# reg-board.net
KiCad netlist of a schematic drawn in EAGLE
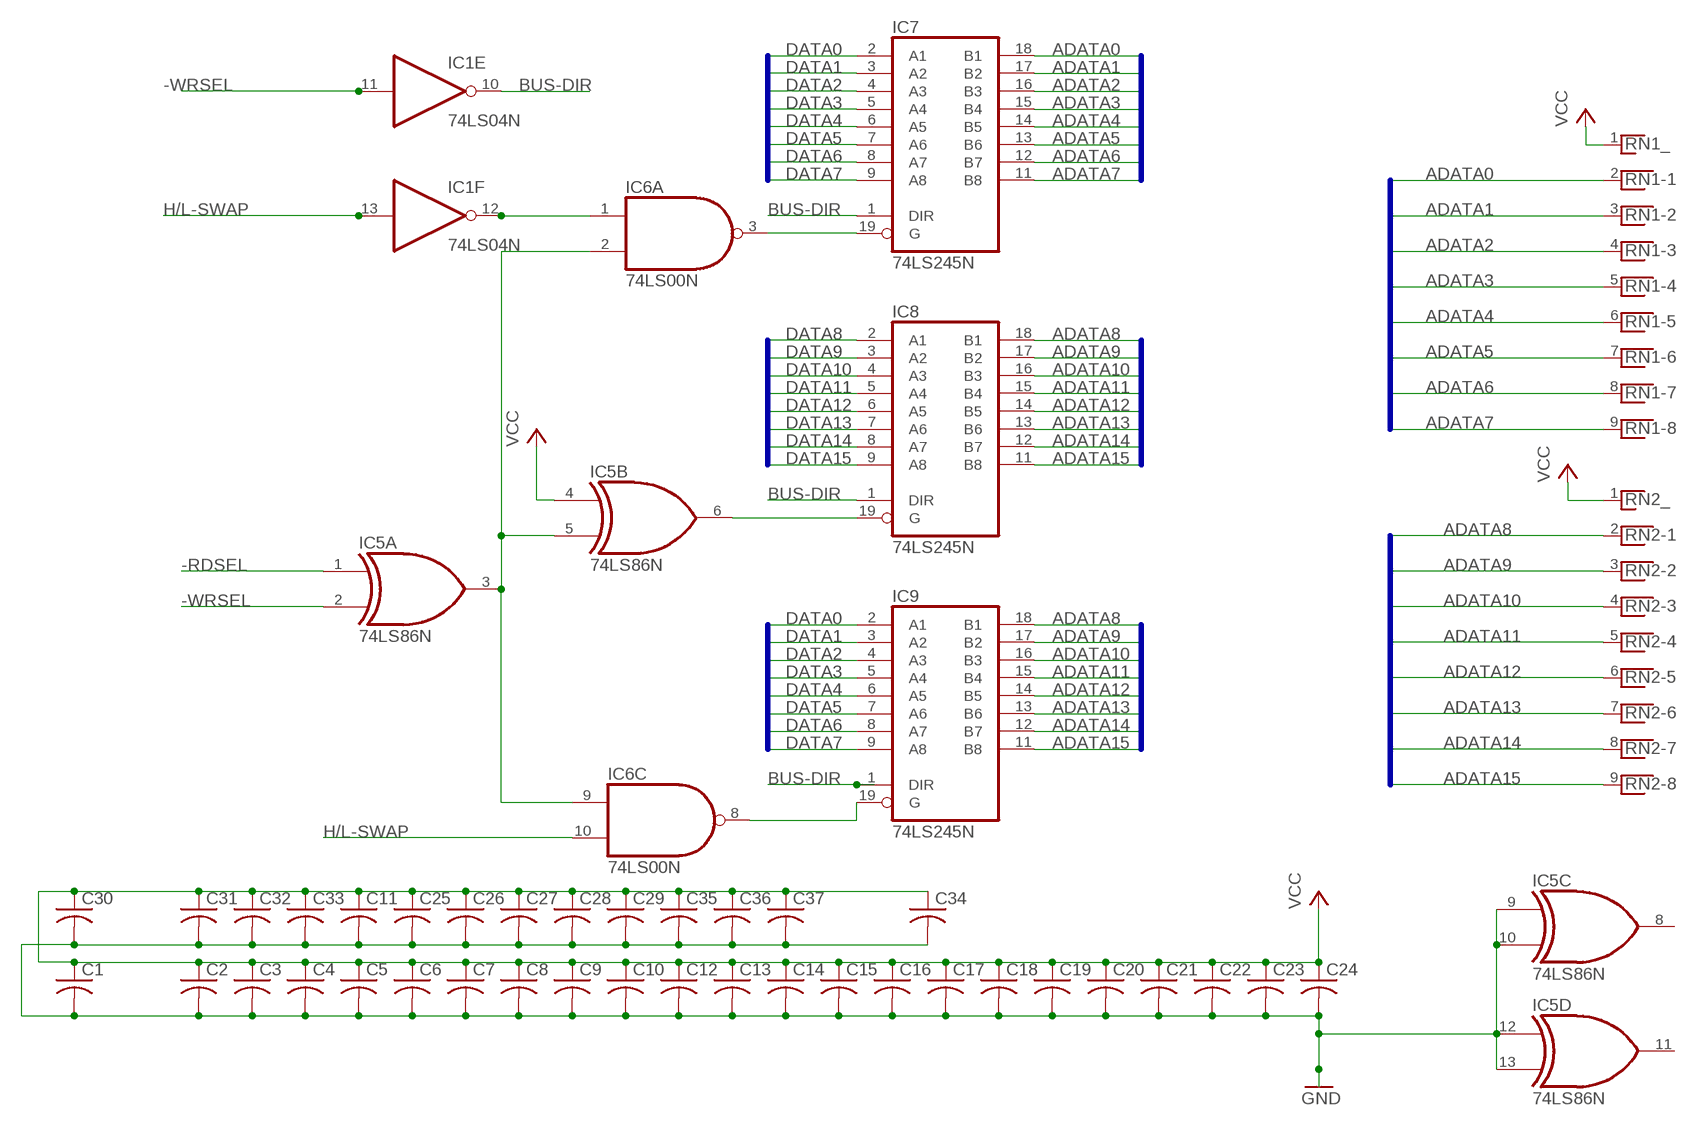
[diagram p0: schematic, sheet 1]
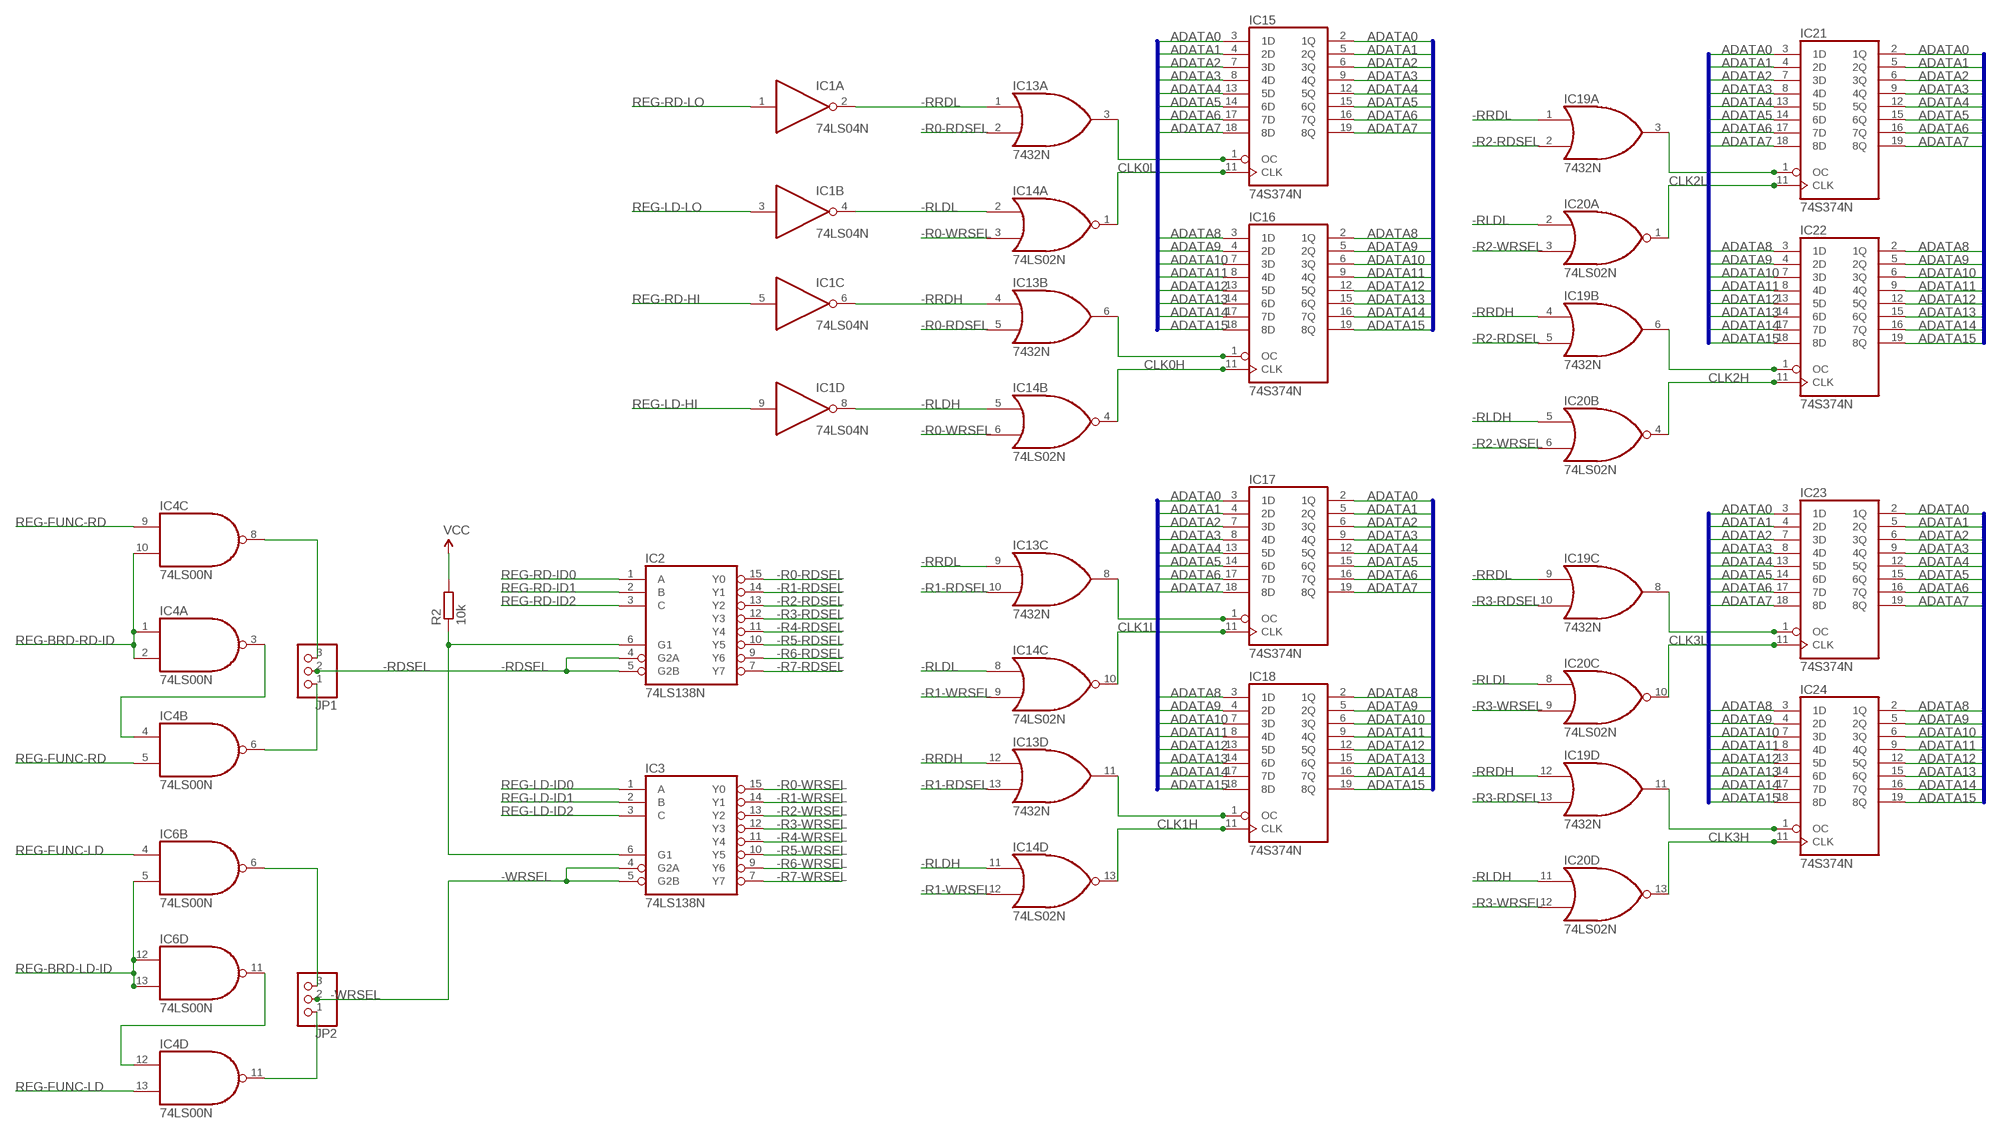
[diagram p1: schematic, sheet 2]
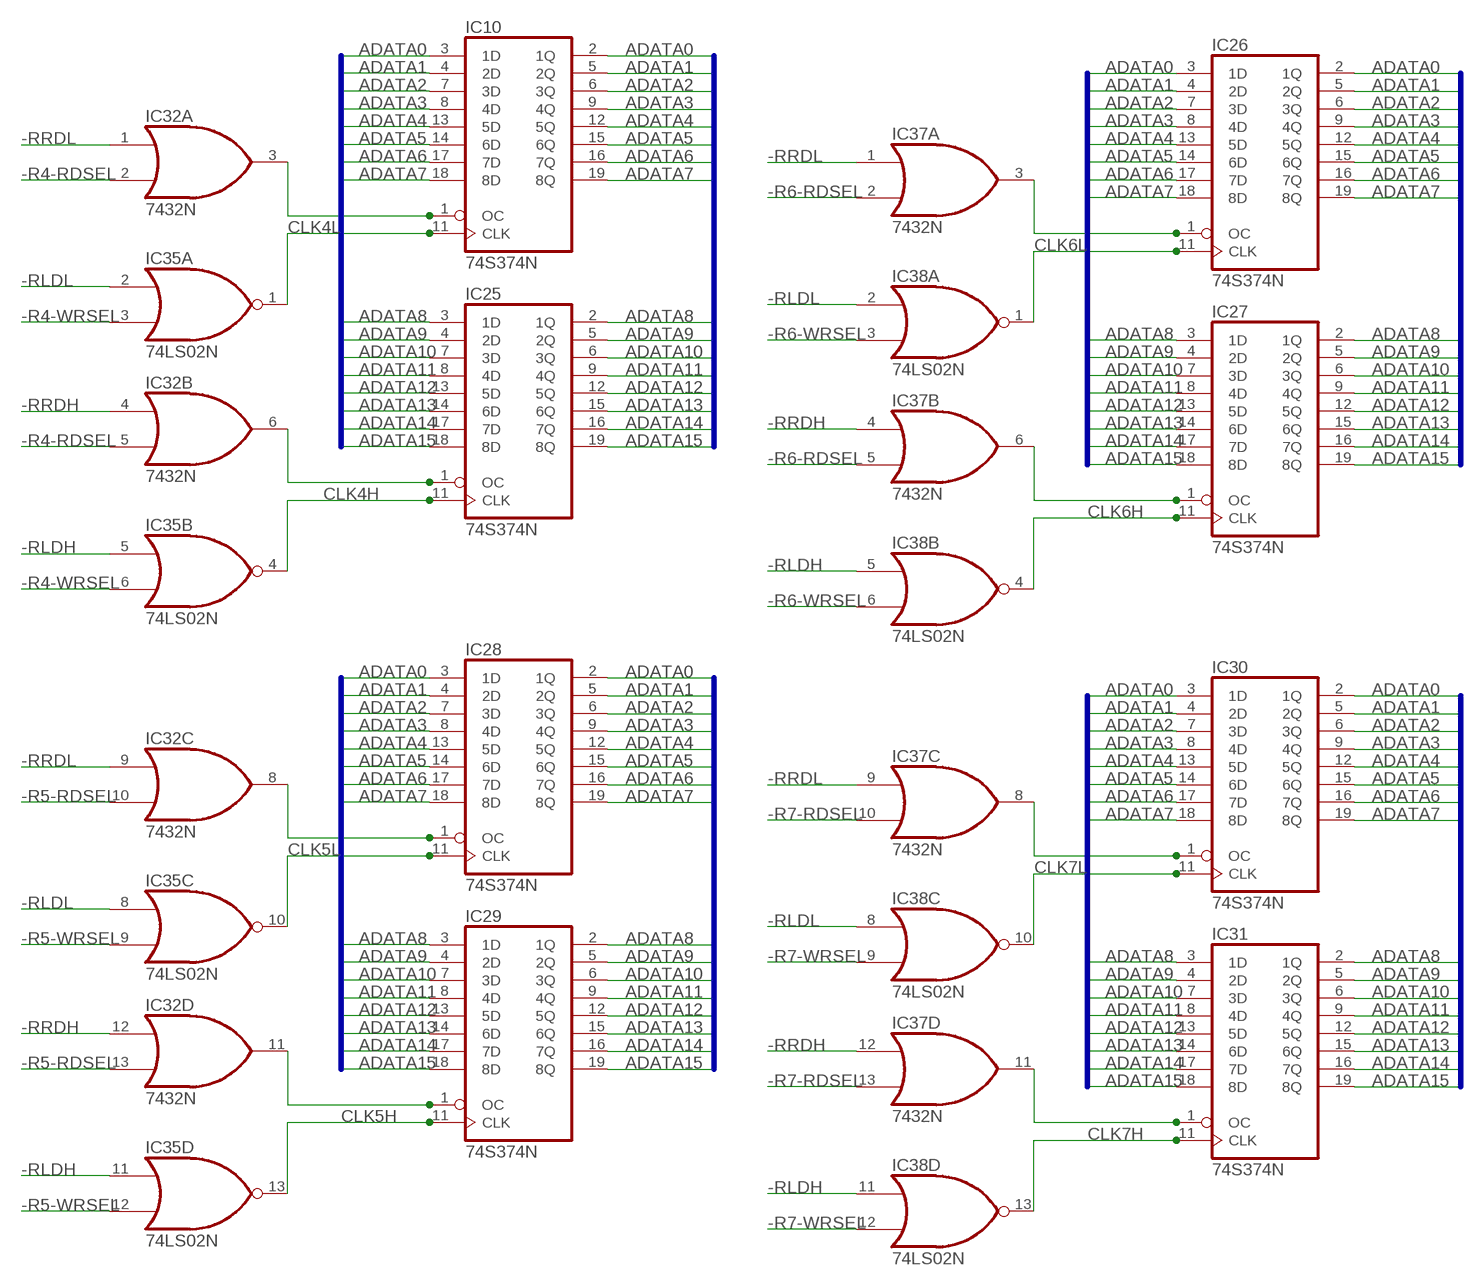
[diagram p2: schematic, sheet 3]
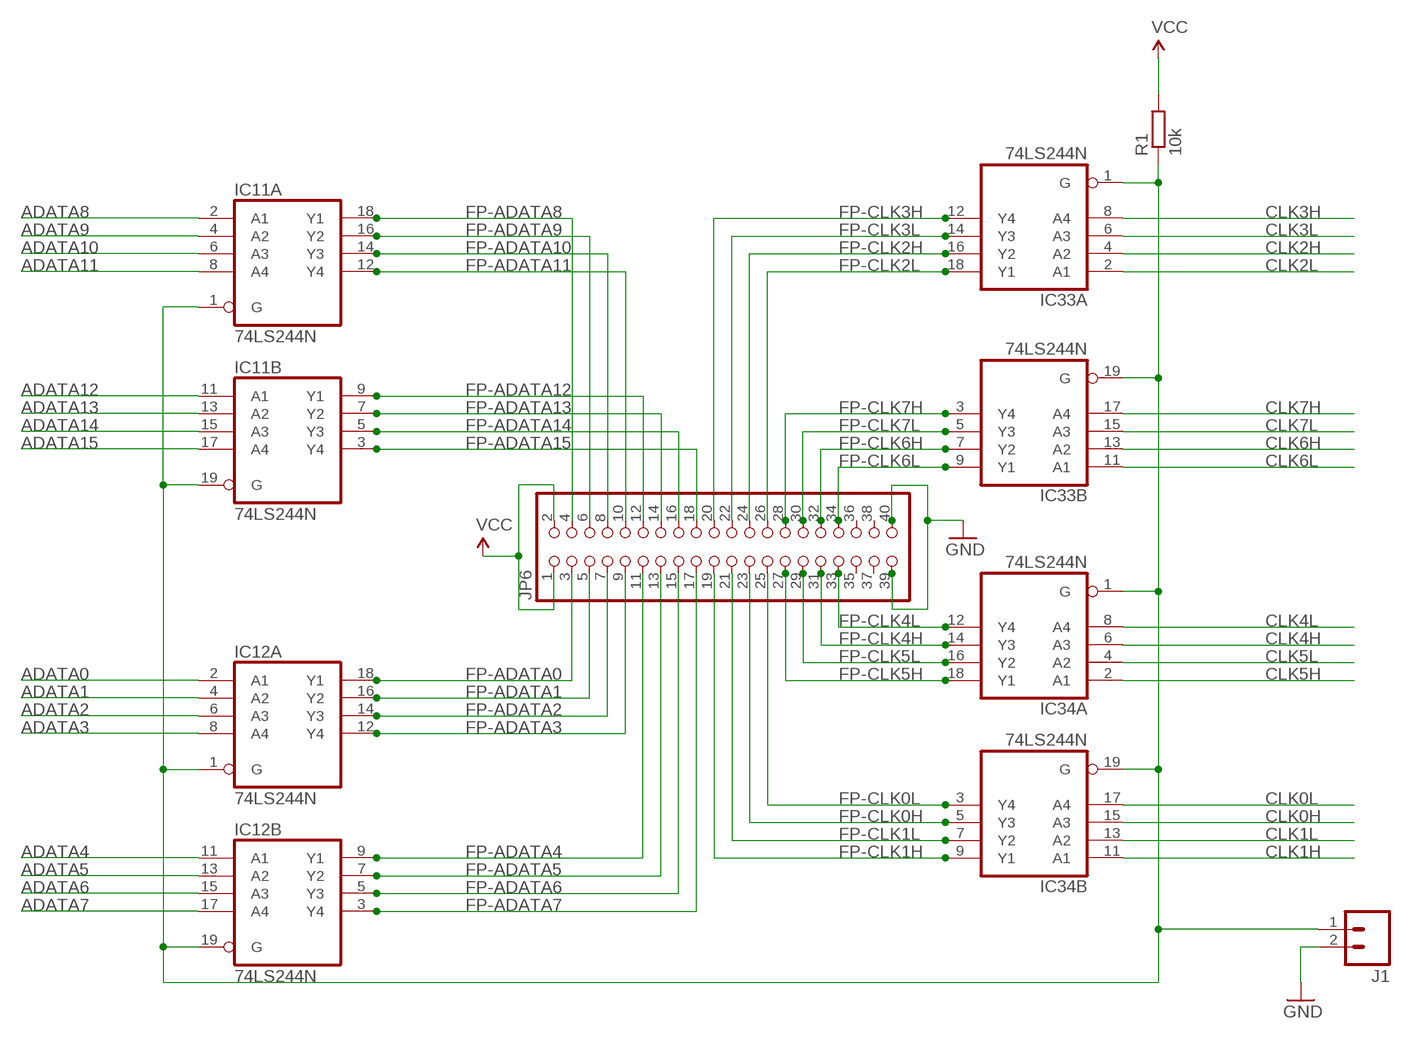
[diagram p3: schematic, sheet 4]
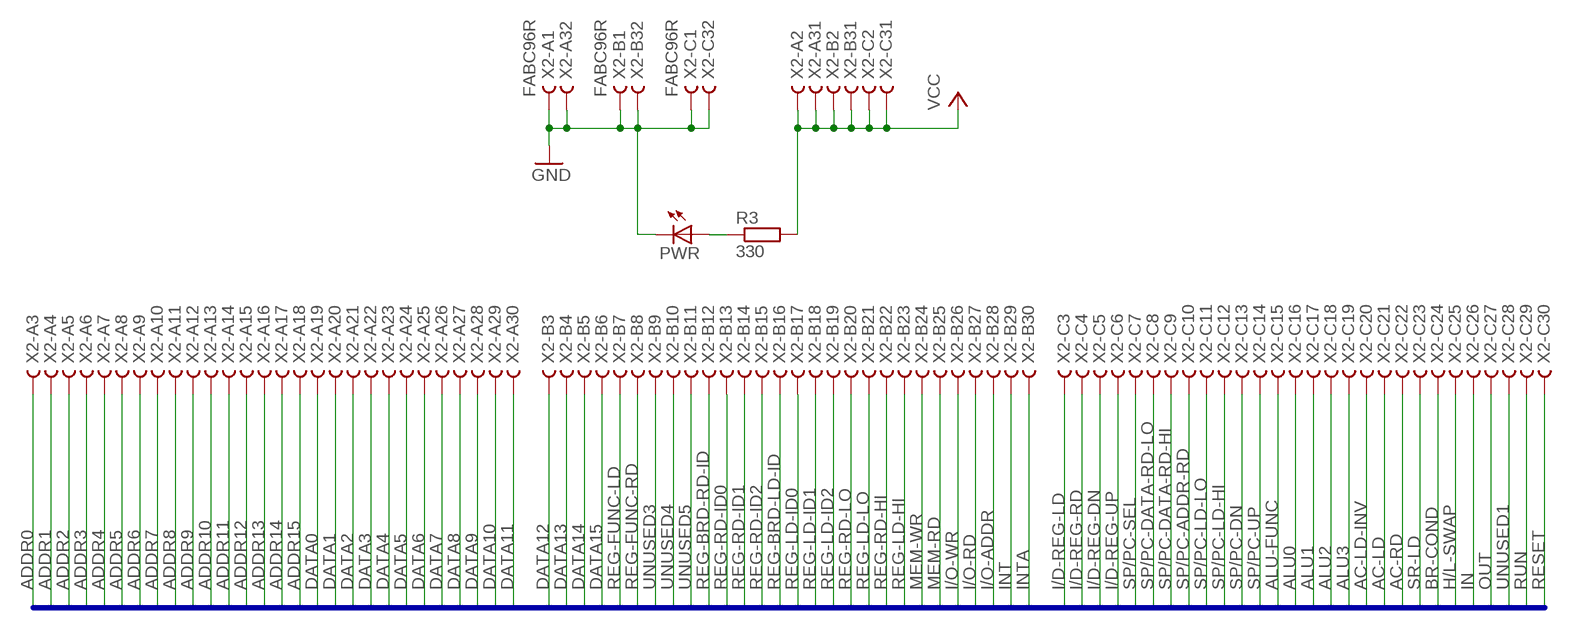
[diagram p4: schematic, sheet 5]

(export (version "E")
  (design (tool "Eeschema 10.0.6"))
  (components
    (comp (ref "IC11")
      (value "74LS244N")
      (footprint "eagle-import:DIL20")
      (libsource (lib "eagle-import") (part "74xx-us_74244NLS"))
    )
    (comp (ref "IC12")
      (value "74LS244N")
      (footprint "eagle-import:DIL20")
      (libsource (lib "eagle-import") (part "74xx-us_74244NLS"))
    )
    (comp (ref "IC33")
      (value "74LS244N")
      (footprint "eagle-import:DIL20")
      (libsource (lib "eagle-import") (part "74xx-us_74244NLS"))
    )
    (comp (ref "IC34")
      (value "74LS244N")
      (footprint "eagle-import:DIL20")
      (libsource (lib "eagle-import") (part "74xx-us_74244NLS"))
    )
    (comp (ref "J1")
      (value "M02PTH")
      (footprint "eagle-import:1X02")
      (libsource (lib "eagle-import") (part "M02PTH"))
    )
    (comp (ref "JP6")
      (value "PINHD-2X20")
      (footprint "eagle-import:2X20")
      (libsource (lib "eagle-import") (part "PINHD-2X20"))
    )
    (comp (ref "R1")
      (value "10k")
      (footprint "eagle-import:0207_10")
      (libsource (lib "eagle-import") (part "R0207/10"))
    )
    (comp (ref "PWR")
      (value "LED5MM")
      (footprint "eagle-import:LED5MM")
      (libsource (lib "eagle-import") (part "LED5MM"))
    )
    (comp (ref "R3")
      (value "330")
      (footprint "eagle-import:0207_10")
      (libsource (lib "eagle-import") (part "R0207/10"))
    )
    (comp (ref "X2")
      (value "FABC96R")
      (footprint "eagle-import:FABC96R")
      (libsource (lib "eagle-import") (part "FABC96R"))
    )
    (comp (ref "C1")
      (value "C-US025-040X050")
      (footprint "eagle-import:C025-040X050")
      (libsource (lib "eagle-import") (part "C-US025-040X050"))
    )
    (comp (ref "C2")
      (value "C-US025-040X050")
      (footprint "eagle-import:C025-040X050")
      (libsource (lib "eagle-import") (part "C-US025-040X050"))
    )
    (comp (ref "C3")
      (value "C-US025-040X050")
      (footprint "eagle-import:C025-040X050")
      (libsource (lib "eagle-import") (part "C-US025-040X050"))
    )
    (comp (ref "C4")
      (value "C-US025-040X050")
      (footprint "eagle-import:C025-040X050")
      (libsource (lib "eagle-import") (part "C-US025-040X050"))
    )
    (comp (ref "C5")
      (value "C-US025-040X050")
      (footprint "eagle-import:C025-040X050")
      (libsource (lib "eagle-import") (part "C-US025-040X050"))
    )
    (comp (ref "C6")
      (value "C-US025-040X050")
      (footprint "eagle-import:C025-040X050")
      (libsource (lib "eagle-import") (part "C-US025-040X050"))
    )
    (comp (ref "C7")
      (value "C-US025-040X050")
      (footprint "eagle-import:C025-040X050")
      (libsource (lib "eagle-import") (part "C-US025-040X050"))
    )
    (comp (ref "C8")
      (value "C-US025-040X050")
      (footprint "eagle-import:C025-040X050")
      (libsource (lib "eagle-import") (part "C-US025-040X050"))
    )
    (comp (ref "C9")
      (value "C-US025-040X050")
      (footprint "eagle-import:C025-040X050")
      (libsource (lib "eagle-import") (part "C-US025-040X050"))
    )
    (comp (ref "C10")
      (value "C-US025-040X050")
      (footprint "eagle-import:C025-040X050")
      (libsource (lib "eagle-import") (part "C-US025-040X050"))
    )
    (comp (ref "C11")
      (value "C-US025-040X050")
      (footprint "eagle-import:C025-040X050")
      (libsource (lib "eagle-import") (part "C-US025-040X050"))
    )
    (comp (ref "C12")
      (value "C-US025-040X050")
      (footprint "eagle-import:C025-040X050")
      (libsource (lib "eagle-import") (part "C-US025-040X050"))
    )
    (comp (ref "C13")
      (value "C-US025-040X050")
      (footprint "eagle-import:C025-040X050")
      (libsource (lib "eagle-import") (part "C-US025-040X050"))
    )
    (comp (ref "C14")
      (value "C-US025-040X050")
      (footprint "eagle-import:C025-040X050")
      (libsource (lib "eagle-import") (part "C-US025-040X050"))
    )
    (comp (ref "C15")
      (value "C-US025-040X050")
      (footprint "eagle-import:C025-040X050")
      (libsource (lib "eagle-import") (part "C-US025-040X050"))
    )
    (comp (ref "C16")
      (value "C-US025-040X050")
      (footprint "eagle-import:C025-040X050")
      (libsource (lib "eagle-import") (part "C-US025-040X050"))
    )
    (comp (ref "C17")
      (value "C-US025-040X050")
      (footprint "eagle-import:C025-040X050")
      (libsource (lib "eagle-import") (part "C-US025-040X050"))
    )
    (comp (ref "C18")
      (value "C-US025-040X050")
      (footprint "eagle-import:C025-040X050")
      (libsource (lib "eagle-import") (part "C-US025-040X050"))
    )
    (comp (ref "C19")
      (value "C-US025-040X050")
      (footprint "eagle-import:C025-040X050")
      (libsource (lib "eagle-import") (part "C-US025-040X050"))
    )
    (comp (ref "C20")
      (value "C-US025-040X050")
      (footprint "eagle-import:C025-040X050")
      (libsource (lib "eagle-import") (part "C-US025-040X050"))
    )
    (comp (ref "C21")
      (value "C-US025-040X050")
      (footprint "eagle-import:C025-040X050")
      (libsource (lib "eagle-import") (part "C-US025-040X050"))
    )
    (comp (ref "C22")
      (value "C-US025-040X050")
      (footprint "eagle-import:C025-040X050")
      (libsource (lib "eagle-import") (part "C-US025-040X050"))
    )
    (comp (ref "C23")
      (value "C-US025-040X050")
      (footprint "eagle-import:C025-040X050")
      (libsource (lib "eagle-import") (part "C-US025-040X050"))
    )
    (comp (ref "C24")
      (value "C-US025-040X050")
      (footprint "eagle-import:C025-040X050")
      (libsource (lib "eagle-import") (part "C-US025-040X050"))
    )
    (comp (ref "C25")
      (value "C-US025-040X050")
      (footprint "eagle-import:C025-040X050")
      (libsource (lib "eagle-import") (part "C-US025-040X050"))
    )
    (comp (ref "C26")
      (value "C-US025-040X050")
      (footprint "eagle-import:C025-040X050")
      (libsource (lib "eagle-import") (part "C-US025-040X050"))
    )
    (comp (ref "C27")
      (value "C-US025-040X050")
      (footprint "eagle-import:C025-040X050")
      (libsource (lib "eagle-import") (part "C-US025-040X050"))
    )
    (comp (ref "C28")
      (value "C-US025-040X050")
      (footprint "eagle-import:C025-040X050")
      (libsource (lib "eagle-import") (part "C-US025-040X050"))
    )
    (comp (ref "C29")
      (value "C-US025-040X050")
      (footprint "eagle-import:C025-040X050")
      (libsource (lib "eagle-import") (part "C-US025-040X050"))
    )
    (comp (ref "C30")
      (value "C-US025-040X050")
      (footprint "eagle-import:C025-040X050")
      (libsource (lib "eagle-import") (part "C-US025-040X050"))
    )
    (comp (ref "C31")
      (value "C-US025-040X050")
      (footprint "eagle-import:C025-040X050")
      (libsource (lib "eagle-import") (part "C-US025-040X050"))
    )
    (comp (ref "C32")
      (value "C-US025-040X050")
      (footprint "eagle-import:C025-040X050")
      (libsource (lib "eagle-import") (part "C-US025-040X050"))
    )
    (comp (ref "C33")
      (value "C-US025-040X050")
      (footprint "eagle-import:C025-040X050")
      (libsource (lib "eagle-import") (part "C-US025-040X050"))
    )
    (comp (ref "C34")
      (value "C-US025-040X050")
      (footprint "eagle-import:C025-040X050")
      (libsource (lib "eagle-import") (part "C-US025-040X050"))
    )
    (comp (ref "C35")
      (value "C-US025-040X050")
      (footprint "eagle-import:C025-040X050")
      (libsource (lib "eagle-import") (part "C-US025-040X050"))
    )
    (comp (ref "C36")
      (value "C-US025-040X050")
      (footprint "eagle-import:C025-040X050")
      (libsource (lib "eagle-import") (part "C-US025-040X050"))
    )
    (comp (ref "C37")
      (value "C-US025-040X050")
      (footprint "eagle-import:C025-040X050")
      (libsource (lib "eagle-import") (part "C-US025-040X050"))
    )
    (comp (ref "IC1")
      (value "74LS04N")
      (footprint "eagle-import:DIL14")
      (libsource (lib "eagle-import") (part "7404NLS"))
    )
    (comp (ref "IC5")
      (value "74LS86N")
      (footprint "eagle-import:DIL14")
      (libsource (lib "eagle-import") (part "7486NLS"))
    )
    (comp (ref "IC6")
      (value "74LS00N")
      (footprint "eagle-import:DIL14")
      (libsource (lib "eagle-import") (part "7400NLS"))
    )
    (comp (ref "IC7")
      (value "74LS245N")
      (footprint "eagle-import:DIL20")
      (libsource (lib "eagle-import") (part "74245NLS"))
    )
    (comp (ref "IC8")
      (value "74LS245N")
      (footprint "eagle-import:DIL20")
      (libsource (lib "eagle-import") (part "74245NLS"))
    )
    (comp (ref "IC9")
      (value "74LS245N")
      (footprint "eagle-import:DIL20")
      (libsource (lib "eagle-import") (part "74245NLS"))
    )
    (comp (ref "RN1")
      (value "RNX8")
      (footprint "eagle-import:RN-9")
      (libsource (lib "eagle-import") (part "RNX8"))
    )
    (comp (ref "RN2")
      (value "RNX8")
      (footprint "eagle-import:RN-9")
      (libsource (lib "eagle-import") (part "RNX8"))
    )
    (comp (ref "IC2")
      (value "74LS138N")
      (footprint "eagle-import:DIL16")
      (libsource (lib "eagle-import") (part "74138NLS"))
    )
    (comp (ref "IC3")
      (value "74LS138N")
      (footprint "eagle-import:DIL16")
      (libsource (lib "eagle-import") (part "74138NLS"))
    )
    (comp (ref "IC4")
      (value "74LS00N")
      (footprint "eagle-import:DIL14")
      (libsource (lib "eagle-import") (part "7400NLS"))
    )
    (comp (ref "IC13")
      (value "7432N")
      (footprint "eagle-import:DIL14")
      (libsource (lib "eagle-import") (part "7432N"))
    )
    (comp (ref "IC14")
      (value "74LS02N")
      (footprint "eagle-import:DIL14")
      (libsource (lib "eagle-import") (part "7402NLS"))
    )
    (comp (ref "IC15")
      (value "74S374N")
      (footprint "eagle-import:DIL20")
      (libsource (lib "eagle-import") (part "74374NS"))
    )
    (comp (ref "IC16")
      (value "74S374N")
      (footprint "eagle-import:DIL20")
      (libsource (lib "eagle-import") (part "74374NS"))
    )
    (comp (ref "IC17")
      (value "74S374N")
      (footprint "eagle-import:DIL20")
      (libsource (lib "eagle-import") (part "74374NS"))
    )
    (comp (ref "IC18")
      (value "74S374N")
      (footprint "eagle-import:DIL20")
      (libsource (lib "eagle-import") (part "74374NS"))
    )
    (comp (ref "IC19")
      (value "7432N")
      (footprint "eagle-import:DIL14")
      (libsource (lib "eagle-import") (part "7432N"))
    )
    (comp (ref "IC20")
      (value "74LS02N")
      (footprint "eagle-import:DIL14")
      (libsource (lib "eagle-import") (part "7402NLS"))
    )
    (comp (ref "IC21")
      (value "74S374N")
      (footprint "eagle-import:DIL20")
      (libsource (lib "eagle-import") (part "74374NS"))
    )
    (comp (ref "IC22")
      (value "74S374N")
      (footprint "eagle-import:DIL20")
      (libsource (lib "eagle-import") (part "74374NS"))
    )
    (comp (ref "IC23")
      (value "74S374N")
      (footprint "eagle-import:DIL20")
      (libsource (lib "eagle-import") (part "74374NS"))
    )
    (comp (ref "IC24")
      (value "74S374N")
      (footprint "eagle-import:DIL20")
      (libsource (lib "eagle-import") (part "74374NS"))
    )
    (comp (ref "JP1")
      (value "PINHD-1X3")
      (footprint "eagle-import:1X03")
      (libsource (lib "eagle-import") (part "PINHD-1X3"))
    )
    (comp (ref "JP2")
      (value "PINHD-1X3")
      (footprint "eagle-import:1X03")
      (libsource (lib "eagle-import") (part "PINHD-1X3"))
    )
    (comp (ref "R2")
      (value "10k")
      (footprint "eagle-import:0207_10")
      (libsource (lib "eagle-import") (part "R0207/10"))
    )
    (comp (ref "IC10")
      (value "74S374N")
      (footprint "eagle-import:DIL20")
      (libsource (lib "eagle-import") (part "74374NS"))
    )
    (comp (ref "IC25")
      (value "74S374N")
      (footprint "eagle-import:DIL20")
      (libsource (lib "eagle-import") (part "74374NS"))
    )
    (comp (ref "IC26")
      (value "74S374N")
      (footprint "eagle-import:DIL20")
      (libsource (lib "eagle-import") (part "74374NS"))
    )
    (comp (ref "IC27")
      (value "74S374N")
      (footprint "eagle-import:DIL20")
      (libsource (lib "eagle-import") (part "74374NS"))
    )
    (comp (ref "IC28")
      (value "74S374N")
      (footprint "eagle-import:DIL20")
      (libsource (lib "eagle-import") (part "74374NS"))
    )
    (comp (ref "IC29")
      (value "74S374N")
      (footprint "eagle-import:DIL20")
      (libsource (lib "eagle-import") (part "74374NS"))
    )
    (comp (ref "IC30")
      (value "74S374N")
      (footprint "eagle-import:DIL20")
      (libsource (lib "eagle-import") (part "74374NS"))
    )
    (comp (ref "IC31")
      (value "74S374N")
      (footprint "eagle-import:DIL20")
      (libsource (lib "eagle-import") (part "74374NS"))
    )
    (comp (ref "IC32")
      (value "7432N")
      (footprint "eagle-import:DIL14")
      (libsource (lib "eagle-import") (part "7432N"))
    )
    (comp (ref "IC35")
      (value "74LS02N")
      (footprint "eagle-import:DIL14")
      (libsource (lib "eagle-import") (part "7402NLS"))
    )
    (comp (ref "IC37")
      (value "7432N")
      (footprint "eagle-import:DIL14")
      (libsource (lib "eagle-import") (part "7432N"))
    )
    (comp (ref "IC38")
      (value "74LS02N")
      (footprint "eagle-import:DIL14")
      (libsource (lib "eagle-import") (part "7402NLS"))
    )
  )
  (nets
    (net (code "1") (name "-R0-RDSEL") (class "Default")
      (node (ref "IC13") (pin "2") (pinfunction "I1_2") (pintype "input"))
      (node (ref "IC13") (pin "5") (pinfunction "I1_5") (pintype "input"))
      (node (ref "IC2") (pin "15") (pinfunction "Y0_15") (pintype "output"))
    )
    (net (code "2") (name "-R0-WRSEL") (class "Default")
      (node (ref "IC14") (pin "3") (pinfunction "I1_3") (pintype "input"))
      (node (ref "IC14") (pin "6") (pinfunction "I1_6") (pintype "input"))
      (node (ref "IC3") (pin "15") (pinfunction "Y0_15") (pintype "output"))
    )
    (net (code "3") (name "-R1-RDSEL") (class "Default")
      (node (ref "IC13") (pin "10") (pinfunction "I1_10") (pintype "input"))
      (node (ref "IC13") (pin "13") (pinfunction "I1_13") (pintype "input"))
      (node (ref "IC2") (pin "14") (pinfunction "Y1_14") (pintype "output"))
    )
    (net (code "4") (name "-R1-WRSEL") (class "Default")
      (node (ref "IC14") (pin "12") (pinfunction "I1_12") (pintype "input"))
      (node (ref "IC14") (pin "9") (pinfunction "I1_9") (pintype "input"))
      (node (ref "IC3") (pin "14") (pinfunction "Y1_14") (pintype "output"))
    )
    (net (code "5") (name "-R2-RDSEL") (class "Default")
      (node (ref "IC19") (pin "2") (pinfunction "I1_2") (pintype "input"))
      (node (ref "IC19") (pin "5") (pinfunction "I1_5") (pintype "input"))
      (node (ref "IC2") (pin "13") (pinfunction "Y2_13") (pintype "output"))
    )
    (net (code "6") (name "-R2-WRSEL") (class "Default")
      (node (ref "IC20") (pin "3") (pinfunction "I1_3") (pintype "input"))
      (node (ref "IC20") (pin "6") (pinfunction "I1_6") (pintype "input"))
      (node (ref "IC3") (pin "13") (pinfunction "Y2_13") (pintype "output"))
    )
    (net (code "7") (name "-R3-RDSEL") (class "Default")
      (node (ref "IC19") (pin "10") (pinfunction "I1_10") (pintype "input"))
      (node (ref "IC19") (pin "13") (pinfunction "I1_13") (pintype "input"))
      (node (ref "IC2") (pin "12") (pinfunction "Y3_12") (pintype "output"))
    )
    (net (code "8") (name "-R3-WRSEL") (class "Default")
      (node (ref "IC20") (pin "12") (pinfunction "I1_12") (pintype "input"))
      (node (ref "IC20") (pin "9") (pinfunction "I1_9") (pintype "input"))
      (node (ref "IC3") (pin "12") (pinfunction "Y3_12") (pintype "output"))
    )
    (net (code "9") (name "-R4-RDSEL") (class "Default")
      (node (ref "IC2") (pin "11") (pinfunction "Y4_11") (pintype "output"))
      (node (ref "IC32") (pin "2") (pinfunction "I1_2") (pintype "input"))
      (node (ref "IC32") (pin "5") (pinfunction "I1_5") (pintype "input"))
    )
    (net (code "10") (name "-R4-WRSEL") (class "Default")
      (node (ref "IC3") (pin "11") (pinfunction "Y4_11") (pintype "output"))
      (node (ref "IC35") (pin "3") (pinfunction "I1_3") (pintype "input"))
      (node (ref "IC35") (pin "6") (pinfunction "I1_6") (pintype "input"))
    )
    (net (code "11") (name "-R5-RDSEL") (class "Default")
      (node (ref "IC2") (pin "10") (pinfunction "Y5_10") (pintype "output"))
      (node (ref "IC32") (pin "10") (pinfunction "I1_10") (pintype "input"))
      (node (ref "IC32") (pin "13") (pinfunction "I1_13") (pintype "input"))
    )
    (net (code "12") (name "-R5-WRSEL") (class "Default")
      (node (ref "IC3") (pin "10") (pinfunction "Y5_10") (pintype "output"))
      (node (ref "IC35") (pin "12") (pinfunction "I1_12") (pintype "input"))
      (node (ref "IC35") (pin "9") (pinfunction "I1_9") (pintype "input"))
    )
    (net (code "13") (name "-R6-RDSEL") (class "Default")
      (node (ref "IC2") (pin "9") (pinfunction "Y6_9") (pintype "output"))
      (node (ref "IC37") (pin "2") (pinfunction "I1_2") (pintype "input"))
      (node (ref "IC37") (pin "5") (pinfunction "I1_5") (pintype "input"))
    )
    (net (code "14") (name "-R6-WRSEL") (class "Default")
      (node (ref "IC3") (pin "9") (pinfunction "Y6_9") (pintype "output"))
      (node (ref "IC38") (pin "3") (pinfunction "I1_3") (pintype "input"))
      (node (ref "IC38") (pin "6") (pinfunction "I1_6") (pintype "input"))
    )
    (net (code "15") (name "-R7-RDSEL") (class "Default")
      (node (ref "IC2") (pin "7") (pinfunction "Y7_7") (pintype "output"))
      (node (ref "IC37") (pin "10") (pinfunction "I1_10") (pintype "input"))
      (node (ref "IC37") (pin "13") (pinfunction "I1_13") (pintype "input"))
    )
    (net (code "16") (name "-R7-WRSEL") (class "Default")
      (node (ref "IC3") (pin "7") (pinfunction "Y7_7") (pintype "output"))
      (node (ref "IC38") (pin "12") (pinfunction "I1_12") (pintype "input"))
      (node (ref "IC38") (pin "9") (pinfunction "I1_9") (pintype "input"))
    )
    (net (code "17") (name "-RDSEL") (class "Default")
      (node (ref "IC2") (pin "4") (pinfunction "G2A_4") (pintype "input"))
      (node (ref "IC2") (pin "5") (pinfunction "G2B_5") (pintype "input"))
      (node (ref "IC5") (pin "1") (pinfunction "I0_1") (pintype "input"))
      (node (ref "JP1") (pin "2") (pinfunction "2_2") (pintype "passive"))
    )
    (net (code "18") (name "-RLDH") (class "Default")
      (node (ref "IC1") (pin "8") (pinfunction "O_8") (pintype "output"))
      (node (ref "IC14") (pin "11") (pinfunction "I0_11") (pintype "input"))
      (node (ref "IC14") (pin "5") (pinfunction "I0_5") (pintype "input"))
      (node (ref "IC20") (pin "11") (pinfunction "I0_11") (pintype "input"))
      (node (ref "IC20") (pin "5") (pinfunction "I0_5") (pintype "input"))
      (node (ref "IC35") (pin "11") (pinfunction "I0_11") (pintype "input"))
      (node (ref "IC35") (pin "5") (pinfunction "I0_5") (pintype "input"))
      (node (ref "IC38") (pin "11") (pinfunction "I0_11") (pintype "input"))
      (node (ref "IC38") (pin "5") (pinfunction "I0_5") (pintype "input"))
    )
    (net (code "19") (name "-RLDL") (class "Default")
      (node (ref "IC1") (pin "4") (pinfunction "O_4") (pintype "output"))
      (node (ref "IC14") (pin "2") (pinfunction "I0_2") (pintype "input"))
      (node (ref "IC14") (pin "8") (pinfunction "I0_8") (pintype "input"))
      (node (ref "IC20") (pin "2") (pinfunction "I0_2") (pintype "input"))
      (node (ref "IC20") (pin "8") (pinfunction "I0_8") (pintype "input"))
      (node (ref "IC35") (pin "2") (pinfunction "I0_2") (pintype "input"))
      (node (ref "IC35") (pin "8") (pinfunction "I0_8") (pintype "input"))
      (node (ref "IC38") (pin "2") (pinfunction "I0_2") (pintype "input"))
      (node (ref "IC38") (pin "8") (pinfunction "I0_8") (pintype "input"))
    )
    (net (code "20") (name "-RRDH") (class "Default")
      (node (ref "IC1") (pin "6") (pinfunction "O_6") (pintype "output"))
      (node (ref "IC13") (pin "12") (pinfunction "I0_12") (pintype "input"))
      (node (ref "IC13") (pin "4") (pinfunction "I0_4") (pintype "input"))
      (node (ref "IC19") (pin "12") (pinfunction "I0_12") (pintype "input"))
      (node (ref "IC19") (pin "4") (pinfunction "I0_4") (pintype "input"))
      (node (ref "IC32") (pin "12") (pinfunction "I0_12") (pintype "input"))
      (node (ref "IC32") (pin "4") (pinfunction "I0_4") (pintype "input"))
      (node (ref "IC37") (pin "12") (pinfunction "I0_12") (pintype "input"))
      (node (ref "IC37") (pin "4") (pinfunction "I0_4") (pintype "input"))
    )
    (net (code "21") (name "-RRDL") (class "Default")
      (node (ref "IC1") (pin "2") (pinfunction "O_2") (pintype "output"))
      (node (ref "IC13") (pin "1") (pinfunction "I0_1") (pintype "input"))
      (node (ref "IC13") (pin "9") (pinfunction "I0_9") (pintype "input"))
      (node (ref "IC19") (pin "1") (pinfunction "I0_1") (pintype "input"))
      (node (ref "IC19") (pin "9") (pinfunction "I0_9") (pintype "input"))
      (node (ref "IC32") (pin "1") (pinfunction "I0_1") (pintype "input"))
      (node (ref "IC32") (pin "9") (pinfunction "I0_9") (pintype "input"))
      (node (ref "IC37") (pin "1") (pinfunction "I0_1") (pintype "input"))
      (node (ref "IC37") (pin "9") (pinfunction "I0_9") (pintype "input"))
    )
    (net (code "22") (name "-WRSEL") (class "Default")
      (node (ref "IC1") (pin "11") (pinfunction "I_11") (pintype "input"))
      (node (ref "IC3") (pin "4") (pinfunction "G2A_4") (pintype "input"))
      (node (ref "IC3") (pin "5") (pinfunction "G2B_5") (pintype "input"))
      (node (ref "IC5") (pin "2") (pinfunction "I1_2") (pintype "input"))
      (node (ref "JP2") (pin "2") (pinfunction "2_2") (pintype "passive"))
    )
    (net (code "23") (name "AC-LD") (class "Default")
      (node (ref "X2") (pin "C21") (pinfunction "B_C21") (pintype "passive"))
    )
    (net (code "24") (name "AC-LD-INV") (class "Default")
      (node (ref "X2") (pin "C20") (pinfunction "B_C20") (pintype "passive"))
    )
    (net (code "25") (name "AC-RD") (class "Default")
      (node (ref "X2") (pin "C22") (pinfunction "B_C22") (pintype "passive"))
    )
    (net (code "26") (name "ADATA0") (class "Default")
      (node (ref "IC10") (pin "2") (pinfunction "1Q_2") (pintype "tri_state"))
      (node (ref "IC10") (pin "3") (pinfunction "1D_3") (pintype "input"))
      (node (ref "IC12") (pin "2") (pinfunction "A1_2") (pintype "input"))
      (node (ref "IC15") (pin "2") (pinfunction "1Q_2") (pintype "tri_state"))
      (node (ref "IC15") (pin "3") (pinfunction "1D_3") (pintype "input"))
      (node (ref "IC17") (pin "2") (pinfunction "1Q_2") (pintype "tri_state"))
      (node (ref "IC17") (pin "3") (pinfunction "1D_3") (pintype "input"))
      (node (ref "IC21") (pin "2") (pinfunction "1Q_2") (pintype "tri_state"))
      (node (ref "IC21") (pin "3") (pinfunction "1D_3") (pintype "input"))
      (node (ref "IC23") (pin "2") (pinfunction "1Q_2") (pintype "tri_state"))
      (node (ref "IC23") (pin "3") (pinfunction "1D_3") (pintype "input"))
      (node (ref "IC26") (pin "2") (pinfunction "1Q_2") (pintype "tri_state"))
      (node (ref "IC26") (pin "3") (pinfunction "1D_3") (pintype "input"))
      (node (ref "IC28") (pin "2") (pinfunction "1Q_2") (pintype "tri_state"))
      (node (ref "IC28") (pin "3") (pinfunction "1D_3") (pintype "input"))
      (node (ref "IC30") (pin "2") (pinfunction "1Q_2") (pintype "tri_state"))
      (node (ref "IC30") (pin "3") (pinfunction "1D_3") (pintype "input"))
      (node (ref "IC7") (pin "18") (pinfunction "B1_18") (pintype "bidirectional"))
      (node (ref "RN1") (pin "2") (pinfunction "1_2") (pintype "passive"))
    )
    (net (code "27") (name "ADATA1") (class "Default")
      (node (ref "IC10") (pin "4") (pinfunction "2D_4") (pintype "input"))
      (node (ref "IC10") (pin "5") (pinfunction "2Q_5") (pintype "tri_state"))
      (node (ref "IC12") (pin "4") (pinfunction "A2_4") (pintype "input"))
      (node (ref "IC15") (pin "4") (pinfunction "2D_4") (pintype "input"))
      (node (ref "IC15") (pin "5") (pinfunction "2Q_5") (pintype "tri_state"))
      (node (ref "IC17") (pin "4") (pinfunction "2D_4") (pintype "input"))
      (node (ref "IC17") (pin "5") (pinfunction "2Q_5") (pintype "tri_state"))
      (node (ref "IC21") (pin "4") (pinfunction "2D_4") (pintype "input"))
      (node (ref "IC21") (pin "5") (pinfunction "2Q_5") (pintype "tri_state"))
      (node (ref "IC23") (pin "4") (pinfunction "2D_4") (pintype "input"))
      (node (ref "IC23") (pin "5") (pinfunction "2Q_5") (pintype "tri_state"))
      (node (ref "IC26") (pin "4") (pinfunction "2D_4") (pintype "input"))
      (node (ref "IC26") (pin "5") (pinfunction "2Q_5") (pintype "tri_state"))
      (node (ref "IC28") (pin "4") (pinfunction "2D_4") (pintype "input"))
      (node (ref "IC28") (pin "5") (pinfunction "2Q_5") (pintype "tri_state"))
      (node (ref "IC30") (pin "4") (pinfunction "2D_4") (pintype "input"))
      (node (ref "IC30") (pin "5") (pinfunction "2Q_5") (pintype "tri_state"))
      (node (ref "IC7") (pin "17") (pinfunction "B2_17") (pintype "bidirectional"))
      (node (ref "RN1") (pin "3") (pinfunction "1_3") (pintype "passive"))
    )
    (net (code "28") (name "ADATA2") (class "Default")
      (node (ref "IC10") (pin "6") (pinfunction "3Q_6") (pintype "tri_state"))
      (node (ref "IC10") (pin "7") (pinfunction "3D_7") (pintype "input"))
      (node (ref "IC12") (pin "6") (pinfunction "A3_6") (pintype "input"))
      (node (ref "IC15") (pin "6") (pinfunction "3Q_6") (pintype "tri_state"))
      (node (ref "IC15") (pin "7") (pinfunction "3D_7") (pintype "input"))
      (node (ref "IC17") (pin "6") (pinfunction "3Q_6") (pintype "tri_state"))
      (node (ref "IC17") (pin "7") (pinfunction "3D_7") (pintype "input"))
      (node (ref "IC21") (pin "6") (pinfunction "3Q_6") (pintype "tri_state"))
      (node (ref "IC21") (pin "7") (pinfunction "3D_7") (pintype "input"))
      (node (ref "IC23") (pin "6") (pinfunction "3Q_6") (pintype "tri_state"))
      (node (ref "IC23") (pin "7") (pinfunction "3D_7") (pintype "input"))
      (node (ref "IC26") (pin "6") (pinfunction "3Q_6") (pintype "tri_state"))
      (node (ref "IC26") (pin "7") (pinfunction "3D_7") (pintype "input"))
      (node (ref "IC28") (pin "6") (pinfunction "3Q_6") (pintype "tri_state"))
      (node (ref "IC28") (pin "7") (pinfunction "3D_7") (pintype "input"))
      (node (ref "IC30") (pin "6") (pinfunction "3Q_6") (pintype "tri_state"))
      (node (ref "IC30") (pin "7") (pinfunction "3D_7") (pintype "input"))
      (node (ref "IC7") (pin "16") (pinfunction "B3_16") (pintype "bidirectional"))
      (node (ref "RN1") (pin "4") (pinfunction "1_4") (pintype "passive"))
    )
    (net (code "29") (name "ADATA3") (class "Default")
      (node (ref "IC10") (pin "8") (pinfunction "4D_8") (pintype "input"))
      (node (ref "IC10") (pin "9") (pinfunction "4Q_9") (pintype "tri_state"))
      (node (ref "IC12") (pin "8") (pinfunction "A4_8") (pintype "input"))
      (node (ref "IC15") (pin "8") (pinfunction "4D_8") (pintype "input"))
      (node (ref "IC15") (pin "9") (pinfunction "4Q_9") (pintype "tri_state"))
      (node (ref "IC17") (pin "8") (pinfunction "4D_8") (pintype "input"))
      (node (ref "IC17") (pin "9") (pinfunction "4Q_9") (pintype "tri_state"))
      (node (ref "IC21") (pin "8") (pinfunction "4D_8") (pintype "input"))
      (node (ref "IC21") (pin "9") (pinfunction "4Q_9") (pintype "tri_state"))
      (node (ref "IC23") (pin "8") (pinfunction "4D_8") (pintype "input"))
      (node (ref "IC23") (pin "9") (pinfunction "4Q_9") (pintype "tri_state"))
      (node (ref "IC26") (pin "8") (pinfunction "4D_8") (pintype "input"))
      (node (ref "IC26") (pin "9") (pinfunction "4Q_9") (pintype "tri_state"))
      (node (ref "IC28") (pin "8") (pinfunction "4D_8") (pintype "input"))
      (node (ref "IC28") (pin "9") (pinfunction "4Q_9") (pintype "tri_state"))
      (node (ref "IC30") (pin "8") (pinfunction "4D_8") (pintype "input"))
      (node (ref "IC30") (pin "9") (pinfunction "4Q_9") (pintype "tri_state"))
      (node (ref "IC7") (pin "15") (pinfunction "B4_15") (pintype "bidirectional"))
      (node (ref "RN1") (pin "5") (pinfunction "1_5") (pintype "passive"))
    )
    (net (code "30") (name "ADATA4") (class "Default")
      (node (ref "IC10") (pin "12") (pinfunction "5Q_12") (pintype "tri_state"))
      (node (ref "IC10") (pin "13") (pinfunction "5D_13") (pintype "input"))
      (node (ref "IC12") (pin "11") (pinfunction "A1_11") (pintype "input"))
      (node (ref "IC15") (pin "12") (pinfunction "5Q_12") (pintype "tri_state"))
      (node (ref "IC15") (pin "13") (pinfunction "5D_13") (pintype "input"))
      (node (ref "IC17") (pin "12") (pinfunction "5Q_12") (pintype "tri_state"))
      (node (ref "IC17") (pin "13") (pinfunction "5D_13") (pintype "input"))
      (node (ref "IC21") (pin "12") (pinfunction "5Q_12") (pintype "tri_state"))
      (node (ref "IC21") (pin "13") (pinfunction "5D_13") (pintype "input"))
      (node (ref "IC23") (pin "12") (pinfunction "5Q_12") (pintype "tri_state"))
      (node (ref "IC23") (pin "13") (pinfunction "5D_13") (pintype "input"))
      (node (ref "IC26") (pin "12") (pinfunction "5Q_12") (pintype "tri_state"))
      (node (ref "IC26") (pin "13") (pinfunction "5D_13") (pintype "input"))
      (node (ref "IC28") (pin "12") (pinfunction "5Q_12") (pintype "tri_state"))
      (node (ref "IC28") (pin "13") (pinfunction "5D_13") (pintype "input"))
      (node (ref "IC30") (pin "12") (pinfunction "5Q_12") (pintype "tri_state"))
      (node (ref "IC30") (pin "13") (pinfunction "5D_13") (pintype "input"))
      (node (ref "IC7") (pin "14") (pinfunction "B5_14") (pintype "bidirectional"))
      (node (ref "RN1") (pin "6") (pinfunction "1_6") (pintype "passive"))
    )
    (net (code "31") (name "ADATA5") (class "Default")
      (node (ref "IC10") (pin "14") (pinfunction "6D_14") (pintype "input"))
      (node (ref "IC10") (pin "15") (pinfunction "6Q_15") (pintype "tri_state"))
      (node (ref "IC12") (pin "13") (pinfunction "A2_13") (pintype "input"))
      (node (ref "IC15") (pin "14") (pinfunction "6D_14") (pintype "input"))
      (node (ref "IC15") (pin "15") (pinfunction "6Q_15") (pintype "tri_state"))
      (node (ref "IC17") (pin "14") (pinfunction "6D_14") (pintype "input"))
      (node (ref "IC17") (pin "15") (pinfunction "6Q_15") (pintype "tri_state"))
      (node (ref "IC21") (pin "14") (pinfunction "6D_14") (pintype "input"))
      (node (ref "IC21") (pin "15") (pinfunction "6Q_15") (pintype "tri_state"))
      (node (ref "IC23") (pin "14") (pinfunction "6D_14") (pintype "input"))
      (node (ref "IC23") (pin "15") (pinfunction "6Q_15") (pintype "tri_state"))
      (node (ref "IC26") (pin "14") (pinfunction "6D_14") (pintype "input"))
      (node (ref "IC26") (pin "15") (pinfunction "6Q_15") (pintype "tri_state"))
      (node (ref "IC28") (pin "14") (pinfunction "6D_14") (pintype "input"))
      (node (ref "IC28") (pin "15") (pinfunction "6Q_15") (pintype "tri_state"))
      (node (ref "IC30") (pin "14") (pinfunction "6D_14") (pintype "input"))
      (node (ref "IC30") (pin "15") (pinfunction "6Q_15") (pintype "tri_state"))
      (node (ref "IC7") (pin "13") (pinfunction "B6_13") (pintype "bidirectional"))
      (node (ref "RN1") (pin "7") (pinfunction "1_7") (pintype "passive"))
    )
    (net (code "32") (name "ADATA6") (class "Default")
      (node (ref "IC10") (pin "16") (pinfunction "7Q_16") (pintype "tri_state"))
      (node (ref "IC10") (pin "17") (pinfunction "7D_17") (pintype "input"))
      (node (ref "IC12") (pin "15") (pinfunction "A3_15") (pintype "input"))
      (node (ref "IC15") (pin "16") (pinfunction "7Q_16") (pintype "tri_state"))
      (node (ref "IC15") (pin "17") (pinfunction "7D_17") (pintype "input"))
      (node (ref "IC17") (pin "16") (pinfunction "7Q_16") (pintype "tri_state"))
      (node (ref "IC17") (pin "17") (pinfunction "7D_17") (pintype "input"))
      (node (ref "IC21") (pin "16") (pinfunction "7Q_16") (pintype "tri_state"))
      (node (ref "IC21") (pin "17") (pinfunction "7D_17") (pintype "input"))
      (node (ref "IC23") (pin "16") (pinfunction "7Q_16") (pintype "tri_state"))
      (node (ref "IC23") (pin "17") (pinfunction "7D_17") (pintype "input"))
      (node (ref "IC26") (pin "16") (pinfunction "7Q_16") (pintype "tri_state"))
      (node (ref "IC26") (pin "17") (pinfunction "7D_17") (pintype "input"))
      (node (ref "IC28") (pin "16") (pinfunction "7Q_16") (pintype "tri_state"))
      (node (ref "IC28") (pin "17") (pinfunction "7D_17") (pintype "input"))
      (node (ref "IC30") (pin "16") (pinfunction "7Q_16") (pintype "tri_state"))
      (node (ref "IC30") (pin "17") (pinfunction "7D_17") (pintype "input"))
      (node (ref "IC7") (pin "12") (pinfunction "B7_12") (pintype "bidirectional"))
      (node (ref "RN1") (pin "8") (pinfunction "1_8") (pintype "passive"))
    )
    (net (code "33") (name "ADATA7") (class "Default")
      (node (ref "IC10") (pin "18") (pinfunction "8D_18") (pintype "input"))
      (node (ref "IC10") (pin "19") (pinfunction "8Q_19") (pintype "tri_state"))
      (node (ref "IC12") (pin "17") (pinfunction "A4_17") (pintype "input"))
      (node (ref "IC15") (pin "18") (pinfunction "8D_18") (pintype "input"))
      (node (ref "IC15") (pin "19") (pinfunction "8Q_19") (pintype "tri_state"))
      (node (ref "IC17") (pin "18") (pinfunction "8D_18") (pintype "input"))
      (node (ref "IC17") (pin "19") (pinfunction "8Q_19") (pintype "tri_state"))
      (node (ref "IC21") (pin "18") (pinfunction "8D_18") (pintype "input"))
      (node (ref "IC21") (pin "19") (pinfunction "8Q_19") (pintype "tri_state"))
      (node (ref "IC23") (pin "18") (pinfunction "8D_18") (pintype "input"))
      (node (ref "IC23") (pin "19") (pinfunction "8Q_19") (pintype "tri_state"))
      (node (ref "IC26") (pin "18") (pinfunction "8D_18") (pintype "input"))
      (node (ref "IC26") (pin "19") (pinfunction "8Q_19") (pintype "tri_state"))
      (node (ref "IC28") (pin "18") (pinfunction "8D_18") (pintype "input"))
      (node (ref "IC28") (pin "19") (pinfunction "8Q_19") (pintype "tri_state"))
      (node (ref "IC30") (pin "18") (pinfunction "8D_18") (pintype "input"))
      (node (ref "IC30") (pin "19") (pinfunction "8Q_19") (pintype "tri_state"))
      (node (ref "IC7") (pin "11") (pinfunction "B8_11") (pintype "bidirectional"))
      (node (ref "RN1") (pin "9") (pinfunction "1_9") (pintype "passive"))
    )
    (net (code "34") (name "ADATA8") (class "Default")
      (node (ref "IC11") (pin "2") (pinfunction "A1_2") (pintype "input"))
      (node (ref "IC16") (pin "2") (pinfunction "1Q_2") (pintype "tri_state"))
      (node (ref "IC16") (pin "3") (pinfunction "1D_3") (pintype "input"))
      (node (ref "IC18") (pin "2") (pinfunction "1Q_2") (pintype "tri_state"))
      (node (ref "IC18") (pin "3") (pinfunction "1D_3") (pintype "input"))
      (node (ref "IC22") (pin "2") (pinfunction "1Q_2") (pintype "tri_state"))
      (node (ref "IC22") (pin "3") (pinfunction "1D_3") (pintype "input"))
      (node (ref "IC24") (pin "2") (pinfunction "1Q_2") (pintype "tri_state"))
      (node (ref "IC24") (pin "3") (pinfunction "1D_3") (pintype "input"))
      (node (ref "IC25") (pin "2") (pinfunction "1Q_2") (pintype "tri_state"))
      (node (ref "IC25") (pin "3") (pinfunction "1D_3") (pintype "input"))
      (node (ref "IC27") (pin "2") (pinfunction "1Q_2") (pintype "tri_state"))
      (node (ref "IC27") (pin "3") (pinfunction "1D_3") (pintype "input"))
      (node (ref "IC29") (pin "2") (pinfunction "1Q_2") (pintype "tri_state"))
      (node (ref "IC29") (pin "3") (pinfunction "1D_3") (pintype "input"))
      (node (ref "IC31") (pin "2") (pinfunction "1Q_2") (pintype "tri_state"))
      (node (ref "IC31") (pin "3") (pinfunction "1D_3") (pintype "input"))
      (node (ref "IC8") (pin "18") (pinfunction "B1_18") (pintype "bidirectional"))
      (node (ref "IC9") (pin "18") (pinfunction "B1_18") (pintype "bidirectional"))
      (node (ref "RN2") (pin "2") (pinfunction "1_2") (pintype "passive"))
    )
    (net (code "35") (name "ADATA9") (class "Default")
      (node (ref "IC11") (pin "4") (pinfunction "A2_4") (pintype "input"))
      (node (ref "IC16") (pin "4") (pinfunction "2D_4") (pintype "input"))
      (node (ref "IC16") (pin "5") (pinfunction "2Q_5") (pintype "tri_state"))
      (node (ref "IC18") (pin "4") (pinfunction "2D_4") (pintype "input"))
      (node (ref "IC18") (pin "5") (pinfunction "2Q_5") (pintype "tri_state"))
      (node (ref "IC22") (pin "4") (pinfunction "2D_4") (pintype "input"))
      (node (ref "IC22") (pin "5") (pinfunction "2Q_5") (pintype "tri_state"))
      (node (ref "IC24") (pin "4") (pinfunction "2D_4") (pintype "input"))
      (node (ref "IC24") (pin "5") (pinfunction "2Q_5") (pintype "tri_state"))
      (node (ref "IC25") (pin "4") (pinfunction "2D_4") (pintype "input"))
      (node (ref "IC25") (pin "5") (pinfunction "2Q_5") (pintype "tri_state"))
      (node (ref "IC27") (pin "4") (pinfunction "2D_4") (pintype "input"))
      (node (ref "IC27") (pin "5") (pinfunction "2Q_5") (pintype "tri_state"))
      (node (ref "IC29") (pin "4") (pinfunction "2D_4") (pintype "input"))
      (node (ref "IC29") (pin "5") (pinfunction "2Q_5") (pintype "tri_state"))
      (node (ref "IC31") (pin "4") (pinfunction "2D_4") (pintype "input"))
      (node (ref "IC31") (pin "5") (pinfunction "2Q_5") (pintype "tri_state"))
      (node (ref "IC8") (pin "17") (pinfunction "B2_17") (pintype "bidirectional"))
      (node (ref "IC9") (pin "17") (pinfunction "B2_17") (pintype "bidirectional"))
      (node (ref "RN2") (pin "3") (pinfunction "1_3") (pintype "passive"))
    )
    (net (code "36") (name "ADATA10") (class "Default")
      (node (ref "IC11") (pin "6") (pinfunction "A3_6") (pintype "input"))
      (node (ref "IC16") (pin "6") (pinfunction "3Q_6") (pintype "tri_state"))
      (node (ref "IC16") (pin "7") (pinfunction "3D_7") (pintype "input"))
      (node (ref "IC18") (pin "6") (pinfunction "3Q_6") (pintype "tri_state"))
      (node (ref "IC18") (pin "7") (pinfunction "3D_7") (pintype "input"))
      (node (ref "IC22") (pin "6") (pinfunction "3Q_6") (pintype "tri_state"))
      (node (ref "IC22") (pin "7") (pinfunction "3D_7") (pintype "input"))
      (node (ref "IC24") (pin "6") (pinfunction "3Q_6") (pintype "tri_state"))
      (node (ref "IC24") (pin "7") (pinfunction "3D_7") (pintype "input"))
      (node (ref "IC25") (pin "6") (pinfunction "3Q_6") (pintype "tri_state"))
      (node (ref "IC25") (pin "7") (pinfunction "3D_7") (pintype "input"))
      (node (ref "IC27") (pin "6") (pinfunction "3Q_6") (pintype "tri_state"))
      (node (ref "IC27") (pin "7") (pinfunction "3D_7") (pintype "input"))
      (node (ref "IC29") (pin "6") (pinfunction "3Q_6") (pintype "tri_state"))
      (node (ref "IC29") (pin "7") (pinfunction "3D_7") (pintype "input"))
      (node (ref "IC31") (pin "6") (pinfunction "3Q_6") (pintype "tri_state"))
      (node (ref "IC31") (pin "7") (pinfunction "3D_7") (pintype "input"))
      (node (ref "IC8") (pin "16") (pinfunction "B3_16") (pintype "bidirectional"))
      (node (ref "IC9") (pin "16") (pinfunction "B3_16") (pintype "bidirectional"))
      (node (ref "RN2") (pin "4") (pinfunction "1_4") (pintype "passive"))
    )
    (net (code "37") (name "ADATA11") (class "Default")
      (node (ref "IC11") (pin "8") (pinfunction "A4_8") (pintype "input"))
      (node (ref "IC16") (pin "8") (pinfunction "4D_8") (pintype "input"))
      (node (ref "IC16") (pin "9") (pinfunction "4Q_9") (pintype "tri_state"))
      (node (ref "IC18") (pin "8") (pinfunction "4D_8") (pintype "input"))
      (node (ref "IC18") (pin "9") (pinfunction "4Q_9") (pintype "tri_state"))
      (node (ref "IC22") (pin "8") (pinfunction "4D_8") (pintype "input"))
      (node (ref "IC22") (pin "9") (pinfunction "4Q_9") (pintype "tri_state"))
      (node (ref "IC24") (pin "8") (pinfunction "4D_8") (pintype "input"))
      (node (ref "IC24") (pin "9") (pinfunction "4Q_9") (pintype "tri_state"))
      (node (ref "IC25") (pin "8") (pinfunction "4D_8") (pintype "input"))
      (node (ref "IC25") (pin "9") (pinfunction "4Q_9") (pintype "tri_state"))
      (node (ref "IC27") (pin "8") (pinfunction "4D_8") (pintype "input"))
      (node (ref "IC27") (pin "9") (pinfunction "4Q_9") (pintype "tri_state"))
      (node (ref "IC29") (pin "8") (pinfunction "4D_8") (pintype "input"))
      (node (ref "IC29") (pin "9") (pinfunction "4Q_9") (pintype "tri_state"))
      (node (ref "IC31") (pin "8") (pinfunction "4D_8") (pintype "input"))
      (node (ref "IC31") (pin "9") (pinfunction "4Q_9") (pintype "tri_state"))
      (node (ref "IC8") (pin "15") (pinfunction "B4_15") (pintype "bidirectional"))
      (node (ref "IC9") (pin "15") (pinfunction "B4_15") (pintype "bidirectional"))
      (node (ref "RN2") (pin "5") (pinfunction "1_5") (pintype "passive"))
    )
    (net (code "38") (name "ADATA12") (class "Default")
      (node (ref "IC11") (pin "11") (pinfunction "A1_11") (pintype "input"))
      (node (ref "IC16") (pin "12") (pinfunction "5Q_12") (pintype "tri_state"))
      (node (ref "IC16") (pin "13") (pinfunction "5D_13") (pintype "input"))
      (node (ref "IC18") (pin "12") (pinfunction "5Q_12") (pintype "tri_state"))
      (node (ref "IC18") (pin "13") (pinfunction "5D_13") (pintype "input"))
      (node (ref "IC22") (pin "12") (pinfunction "5Q_12") (pintype "tri_state"))
      (node (ref "IC22") (pin "13") (pinfunction "5D_13") (pintype "input"))
      (node (ref "IC24") (pin "12") (pinfunction "5Q_12") (pintype "tri_state"))
      (node (ref "IC24") (pin "13") (pinfunction "5D_13") (pintype "input"))
      (node (ref "IC25") (pin "12") (pinfunction "5Q_12") (pintype "tri_state"))
      (node (ref "IC25") (pin "13") (pinfunction "5D_13") (pintype "input"))
      (node (ref "IC27") (pin "12") (pinfunction "5Q_12") (pintype "tri_state"))
      (node (ref "IC27") (pin "13") (pinfunction "5D_13") (pintype "input"))
      (node (ref "IC29") (pin "12") (pinfunction "5Q_12") (pintype "tri_state"))
      (node (ref "IC29") (pin "13") (pinfunction "5D_13") (pintype "input"))
      (node (ref "IC31") (pin "12") (pinfunction "5Q_12") (pintype "tri_state"))
      (node (ref "IC31") (pin "13") (pinfunction "5D_13") (pintype "input"))
      (node (ref "IC8") (pin "14") (pinfunction "B5_14") (pintype "bidirectional"))
      (node (ref "IC9") (pin "14") (pinfunction "B5_14") (pintype "bidirectional"))
      (node (ref "RN2") (pin "6") (pinfunction "1_6") (pintype "passive"))
    )
    (net (code "39") (name "ADATA13") (class "Default")
      (node (ref "IC11") (pin "13") (pinfunction "A2_13") (pintype "input"))
      (node (ref "IC16") (pin "14") (pinfunction "6D_14") (pintype "input"))
      (node (ref "IC16") (pin "15") (pinfunction "6Q_15") (pintype "tri_state"))
      (node (ref "IC18") (pin "14") (pinfunction "6D_14") (pintype "input"))
      (node (ref "IC18") (pin "15") (pinfunction "6Q_15") (pintype "tri_state"))
      (node (ref "IC22") (pin "14") (pinfunction "6D_14") (pintype "input"))
      (node (ref "IC22") (pin "15") (pinfunction "6Q_15") (pintype "tri_state"))
      (node (ref "IC24") (pin "14") (pinfunction "6D_14") (pintype "input"))
      (node (ref "IC24") (pin "15") (pinfunction "6Q_15") (pintype "tri_state"))
      (node (ref "IC25") (pin "14") (pinfunction "6D_14") (pintype "input"))
      (node (ref "IC25") (pin "15") (pinfunction "6Q_15") (pintype "tri_state"))
      (node (ref "IC27") (pin "14") (pinfunction "6D_14") (pintype "input"))
      (node (ref "IC27") (pin "15") (pinfunction "6Q_15") (pintype "tri_state"))
      (node (ref "IC29") (pin "14") (pinfunction "6D_14") (pintype "input"))
      (node (ref "IC29") (pin "15") (pinfunction "6Q_15") (pintype "tri_state"))
      (node (ref "IC31") (pin "14") (pinfunction "6D_14") (pintype "input"))
      (node (ref "IC31") (pin "15") (pinfunction "6Q_15") (pintype "tri_state"))
      (node (ref "IC8") (pin "13") (pinfunction "B6_13") (pintype "bidirectional"))
      (node (ref "IC9") (pin "13") (pinfunction "B6_13") (pintype "bidirectional"))
      (node (ref "RN2") (pin "7") (pinfunction "1_7") (pintype "passive"))
    )
    (net (code "40") (name "ADATA14") (class "Default")
      (node (ref "IC11") (pin "15") (pinfunction "A3_15") (pintype "input"))
      (node (ref "IC16") (pin "16") (pinfunction "7Q_16") (pintype "tri_state"))
      (node (ref "IC16") (pin "17") (pinfunction "7D_17") (pintype "input"))
      (node (ref "IC18") (pin "16") (pinfunction "7Q_16") (pintype "tri_state"))
      (node (ref "IC18") (pin "17") (pinfunction "7D_17") (pintype "input"))
      (node (ref "IC22") (pin "16") (pinfunction "7Q_16") (pintype "tri_state"))
      (node (ref "IC22") (pin "17") (pinfunction "7D_17") (pintype "input"))
      (node (ref "IC24") (pin "16") (pinfunction "7Q_16") (pintype "tri_state"))
      (node (ref "IC24") (pin "17") (pinfunction "7D_17") (pintype "input"))
      (node (ref "IC25") (pin "16") (pinfunction "7Q_16") (pintype "tri_state"))
      (node (ref "IC25") (pin "17") (pinfunction "7D_17") (pintype "input"))
      (node (ref "IC27") (pin "16") (pinfunction "7Q_16") (pintype "tri_state"))
      (node (ref "IC27") (pin "17") (pinfunction "7D_17") (pintype "input"))
      (node (ref "IC29") (pin "16") (pinfunction "7Q_16") (pintype "tri_state"))
      (node (ref "IC29") (pin "17") (pinfunction "7D_17") (pintype "input"))
      (node (ref "IC31") (pin "16") (pinfunction "7Q_16") (pintype "tri_state"))
      (node (ref "IC31") (pin "17") (pinfunction "7D_17") (pintype "input"))
      (node (ref "IC8") (pin "12") (pinfunction "B7_12") (pintype "bidirectional"))
      (node (ref "IC9") (pin "12") (pinfunction "B7_12") (pintype "bidirectional"))
      (node (ref "RN2") (pin "8") (pinfunction "1_8") (pintype "passive"))
    )
    (net (code "41") (name "ADATA15") (class "Default")
      (node (ref "IC11") (pin "17") (pinfunction "A4_17") (pintype "input"))
      (node (ref "IC16") (pin "18") (pinfunction "8D_18") (pintype "input"))
      (node (ref "IC16") (pin "19") (pinfunction "8Q_19") (pintype "tri_state"))
      (node (ref "IC18") (pin "18") (pinfunction "8D_18") (pintype "input"))
      (node (ref "IC18") (pin "19") (pinfunction "8Q_19") (pintype "tri_state"))
      (node (ref "IC22") (pin "18") (pinfunction "8D_18") (pintype "input"))
      (node (ref "IC22") (pin "19") (pinfunction "8Q_19") (pintype "tri_state"))
      (node (ref "IC24") (pin "18") (pinfunction "8D_18") (pintype "input"))
      (node (ref "IC24") (pin "19") (pinfunction "8Q_19") (pintype "tri_state"))
      (node (ref "IC25") (pin "18") (pinfunction "8D_18") (pintype "input"))
      (node (ref "IC25") (pin "19") (pinfunction "8Q_19") (pintype "tri_state"))
      (node (ref "IC27") (pin "18") (pinfunction "8D_18") (pintype "input"))
      (node (ref "IC27") (pin "19") (pinfunction "8Q_19") (pintype "tri_state"))
      (node (ref "IC29") (pin "18") (pinfunction "8D_18") (pintype "input"))
      (node (ref "IC29") (pin "19") (pinfunction "8Q_19") (pintype "tri_state"))
      (node (ref "IC31") (pin "18") (pinfunction "8D_18") (pintype "input"))
      (node (ref "IC31") (pin "19") (pinfunction "8Q_19") (pintype "tri_state"))
      (node (ref "IC8") (pin "11") (pinfunction "B8_11") (pintype "bidirectional"))
      (node (ref "IC9") (pin "11") (pinfunction "B8_11") (pintype "bidirectional"))
      (node (ref "RN2") (pin "9") (pinfunction "1_9") (pintype "passive"))
    )
    (net (code "42") (name "ADDR0") (class "Default")
      (node (ref "X2") (pin "A3") (pinfunction "B_A3") (pintype "passive"))
    )
    (net (code "43") (name "ADDR1") (class "Default")
      (node (ref "X2") (pin "A4") (pinfunction "B_A4") (pintype "passive"))
    )
    (net (code "44") (name "ADDR2") (class "Default")
      (node (ref "X2") (pin "A5") (pinfunction "B_A5") (pintype "passive"))
    )
    (net (code "45") (name "ADDR3") (class "Default")
      (node (ref "X2") (pin "A6") (pinfunction "B_A6") (pintype "passive"))
    )
    (net (code "46") (name "ADDR4") (class "Default")
      (node (ref "X2") (pin "A7") (pinfunction "B_A7") (pintype "passive"))
    )
    (net (code "47") (name "ADDR5") (class "Default")
      (node (ref "X2") (pin "A8") (pinfunction "B_A8") (pintype "passive"))
    )
    (net (code "48") (name "ADDR6") (class "Default")
      (node (ref "X2") (pin "A9") (pinfunction "B_A9") (pintype "passive"))
    )
    (net (code "49") (name "ADDR7") (class "Default")
      (node (ref "X2") (pin "A10") (pinfunction "B_A10") (pintype "passive"))
    )
    (net (code "50") (name "ADDR8") (class "Default")
      (node (ref "X2") (pin "A11") (pinfunction "B_A11") (pintype "passive"))
    )
    (net (code "51") (name "ADDR9") (class "Default")
      (node (ref "X2") (pin "A12") (pinfunction "B_A12") (pintype "passive"))
    )
    (net (code "52") (name "ADDR10") (class "Default")
      (node (ref "X2") (pin "A13") (pinfunction "B_A13") (pintype "passive"))
    )
    (net (code "53") (name "ADDR11") (class "Default")
      (node (ref "X2") (pin "A14") (pinfunction "B_A14") (pintype "passive"))
    )
    (net (code "54") (name "ADDR12") (class "Default")
      (node (ref "X2") (pin "A15") (pinfunction "B_A15") (pintype "passive"))
    )
    (net (code "55") (name "ADDR13") (class "Default")
      (node (ref "X2") (pin "A16") (pinfunction "B_A16") (pintype "passive"))
    )
    (net (code "56") (name "ADDR14") (class "Default")
      (node (ref "X2") (pin "A17") (pinfunction "B_A17") (pintype "passive"))
    )
    (net (code "57") (name "ADDR15") (class "Default")
      (node (ref "X2") (pin "A18") (pinfunction "B_A18") (pintype "passive"))
    )
    (net (code "58") (name "ALU-FUNC") (class "Default")
      (node (ref "X2") (pin "C15") (pinfunction "B_C15") (pintype "passive"))
    )
    (net (code "59") (name "ALU0") (class "Default")
      (node (ref "X2") (pin "C16") (pinfunction "B_C16") (pintype "passive"))
    )
    (net (code "60") (name "ALU1") (class "Default")
      (node (ref "X2") (pin "C17") (pinfunction "B_C17") (pintype "passive"))
    )
    (net (code "61") (name "ALU2") (class "Default")
      (node (ref "X2") (pin "C18") (pinfunction "B_C18") (pintype "passive"))
    )
    (net (code "62") (name "ALU3") (class "Default")
      (node (ref "X2") (pin "C19") (pinfunction "B_C19") (pintype "passive"))
    )
    (net (code "63") (name "BR-COND") (class "Default")
      (node (ref "X2") (pin "C24") (pinfunction "B_C24") (pintype "passive"))
    )
    (net (code "64") (name "BUS-DIR") (class "Default")
      (node (ref "IC1") (pin "10") (pinfunction "O_10") (pintype "output"))
      (node (ref "IC7") (pin "1") (pinfunction "DIR_1") (pintype "input"))
      (node (ref "IC8") (pin "1") (pinfunction "DIR_1") (pintype "input"))
      (node (ref "IC9") (pin "1") (pinfunction "DIR_1") (pintype "input"))
    )
    (net (code "65") (name "CLK0H") (class "Default")
      (node (ref "IC14") (pin "4") (pinfunction "O_4") (pintype "output"))
      (node (ref "IC16") (pin "11") (pinfunction "CLK_11") (pintype "input"))
      (node (ref "IC34") (pin "15") (pinfunction "A3_15") (pintype "input"))
    )
    (net (code "66") (name "CLK0L") (class "Default")
      (node (ref "IC14") (pin "1") (pinfunction "O_1") (pintype "output"))
      (node (ref "IC15") (pin "11") (pinfunction "CLK_11") (pintype "input"))
      (node (ref "IC34") (pin "17") (pinfunction "A4_17") (pintype "input"))
    )
    (net (code "67") (name "CLK1H") (class "Default")
      (node (ref "IC14") (pin "13") (pinfunction "O_13") (pintype "output"))
      (node (ref "IC18") (pin "11") (pinfunction "CLK_11") (pintype "input"))
      (node (ref "IC34") (pin "11") (pinfunction "A1_11") (pintype "input"))
    )
    (net (code "68") (name "CLK1L") (class "Default")
      (node (ref "IC14") (pin "10") (pinfunction "O_10") (pintype "output"))
      (node (ref "IC17") (pin "11") (pinfunction "CLK_11") (pintype "input"))
      (node (ref "IC34") (pin "13") (pinfunction "A2_13") (pintype "input"))
    )
    (net (code "69") (name "CLK2H") (class "Default")
      (node (ref "IC20") (pin "4") (pinfunction "O_4") (pintype "output"))
      (node (ref "IC22") (pin "11") (pinfunction "CLK_11") (pintype "input"))
      (node (ref "IC33") (pin "4") (pinfunction "A2_4") (pintype "input"))
    )
    (net (code "70") (name "CLK2L") (class "Default")
      (node (ref "IC20") (pin "1") (pinfunction "O_1") (pintype "output"))
      (node (ref "IC21") (pin "11") (pinfunction "CLK_11") (pintype "input"))
      (node (ref "IC33") (pin "2") (pinfunction "A1_2") (pintype "input"))
    )
    (net (code "71") (name "CLK3H") (class "Default")
      (node (ref "IC20") (pin "13") (pinfunction "O_13") (pintype "output"))
      (node (ref "IC24") (pin "11") (pinfunction "CLK_11") (pintype "input"))
      (node (ref "IC33") (pin "8") (pinfunction "A4_8") (pintype "input"))
    )
    (net (code "72") (name "CLK3L") (class "Default")
      (node (ref "IC20") (pin "10") (pinfunction "O_10") (pintype "output"))
      (node (ref "IC23") (pin "11") (pinfunction "CLK_11") (pintype "input"))
      (node (ref "IC33") (pin "6") (pinfunction "A3_6") (pintype "input"))
    )
    (net (code "73") (name "CLK4H") (class "Default")
      (node (ref "IC25") (pin "11") (pinfunction "CLK_11") (pintype "input"))
      (node (ref "IC34") (pin "6") (pinfunction "A3_6") (pintype "input"))
      (node (ref "IC35") (pin "4") (pinfunction "O_4") (pintype "output"))
    )
    (net (code "74") (name "CLK4L") (class "Default")
      (node (ref "IC10") (pin "11") (pinfunction "CLK_11") (pintype "input"))
      (node (ref "IC34") (pin "8") (pinfunction "A4_8") (pintype "input"))
      (node (ref "IC35") (pin "1") (pinfunction "O_1") (pintype "output"))
    )
    (net (code "75") (name "CLK5H") (class "Default")
      (node (ref "IC29") (pin "11") (pinfunction "CLK_11") (pintype "input"))
      (node (ref "IC34") (pin "2") (pinfunction "A1_2") (pintype "input"))
      (node (ref "IC35") (pin "13") (pinfunction "O_13") (pintype "output"))
    )
    (net (code "76") (name "CLK5L") (class "Default")
      (node (ref "IC28") (pin "11") (pinfunction "CLK_11") (pintype "input"))
      (node (ref "IC34") (pin "4") (pinfunction "A2_4") (pintype "input"))
      (node (ref "IC35") (pin "10") (pinfunction "O_10") (pintype "output"))
    )
    (net (code "77") (name "CLK6H") (class "Default")
      (node (ref "IC27") (pin "11") (pinfunction "CLK_11") (pintype "input"))
      (node (ref "IC33") (pin "13") (pinfunction "A2_13") (pintype "input"))
      (node (ref "IC38") (pin "4") (pinfunction "O_4") (pintype "output"))
    )
    (net (code "78") (name "CLK6L") (class "Default")
      (node (ref "IC26") (pin "11") (pinfunction "CLK_11") (pintype "input"))
      (node (ref "IC33") (pin "11") (pinfunction "A1_11") (pintype "input"))
      (node (ref "IC38") (pin "1") (pinfunction "O_1") (pintype "output"))
    )
    (net (code "79") (name "CLK7H") (class "Default")
      (node (ref "IC31") (pin "11") (pinfunction "CLK_11") (pintype "input"))
      (node (ref "IC33") (pin "17") (pinfunction "A4_17") (pintype "input"))
      (node (ref "IC38") (pin "13") (pinfunction "O_13") (pintype "output"))
    )
    (net (code "80") (name "CLK7L") (class "Default")
      (node (ref "IC30") (pin "11") (pinfunction "CLK_11") (pintype "input"))
      (node (ref "IC33") (pin "15") (pinfunction "A3_15") (pintype "input"))
      (node (ref "IC38") (pin "10") (pinfunction "O_10") (pintype "output"))
    )
    (net (code "81") (name "DATA0") (class "Default")
      (node (ref "IC7") (pin "2") (pinfunction "A1_2") (pintype "bidirectional"))
      (node (ref "IC9") (pin "2") (pinfunction "A1_2") (pintype "bidirectional"))
      (node (ref "X2") (pin "A19") (pinfunction "B_A19") (pintype "passive"))
    )
    (net (code "82") (name "DATA1") (class "Default")
      (node (ref "IC7") (pin "3") (pinfunction "A2_3") (pintype "bidirectional"))
      (node (ref "IC9") (pin "3") (pinfunction "A2_3") (pintype "bidirectional"))
      (node (ref "X2") (pin "A20") (pinfunction "B_A20") (pintype "passive"))
    )
    (net (code "83") (name "DATA2") (class "Default")
      (node (ref "IC7") (pin "4") (pinfunction "A3_4") (pintype "bidirectional"))
      (node (ref "IC9") (pin "4") (pinfunction "A3_4") (pintype "bidirectional"))
      (node (ref "X2") (pin "A21") (pinfunction "B_A21") (pintype "passive"))
    )
    (net (code "84") (name "DATA3") (class "Default")
      (node (ref "IC7") (pin "5") (pinfunction "A4_5") (pintype "bidirectional"))
      (node (ref "IC9") (pin "5") (pinfunction "A4_5") (pintype "bidirectional"))
      (node (ref "X2") (pin "A22") (pinfunction "B_A22") (pintype "passive"))
    )
    (net (code "85") (name "DATA4") (class "Default")
      (node (ref "IC7") (pin "6") (pinfunction "A5_6") (pintype "bidirectional"))
      (node (ref "IC9") (pin "6") (pinfunction "A5_6") (pintype "bidirectional"))
      (node (ref "X2") (pin "A23") (pinfunction "B_A23") (pintype "passive"))
    )
    (net (code "86") (name "DATA5") (class "Default")
      (node (ref "IC7") (pin "7") (pinfunction "A6_7") (pintype "bidirectional"))
      (node (ref "IC9") (pin "7") (pinfunction "A6_7") (pintype "bidirectional"))
      (node (ref "X2") (pin "A24") (pinfunction "B_A24") (pintype "passive"))
    )
    (net (code "87") (name "DATA6") (class "Default")
      (node (ref "IC7") (pin "8") (pinfunction "A7_8") (pintype "bidirectional"))
      (node (ref "IC9") (pin "8") (pinfunction "A7_8") (pintype "bidirectional"))
      (node (ref "X2") (pin "A25") (pinfunction "B_A25") (pintype "passive"))
    )
    (net (code "88") (name "DATA7") (class "Default")
      (node (ref "IC7") (pin "9") (pinfunction "A8_9") (pintype "bidirectional"))
      (node (ref "IC9") (pin "9") (pinfunction "A8_9") (pintype "bidirectional"))
      (node (ref "X2") (pin "A26") (pinfunction "B_A26") (pintype "passive"))
    )
    (net (code "89") (name "DATA8") (class "Default")
      (node (ref "IC8") (pin "2") (pinfunction "A1_2") (pintype "bidirectional"))
      (node (ref "X2") (pin "A27") (pinfunction "B_A27") (pintype "passive"))
    )
    (net (code "90") (name "DATA9") (class "Default")
      (node (ref "IC8") (pin "3") (pinfunction "A2_3") (pintype "bidirectional"))
      (node (ref "X2") (pin "A28") (pinfunction "B_A28") (pintype "passive"))
    )
    (net (code "91") (name "DATA10") (class "Default")
      (node (ref "IC8") (pin "4") (pinfunction "A3_4") (pintype "bidirectional"))
      (node (ref "X2") (pin "A29") (pinfunction "B_A29") (pintype "passive"))
    )
    (net (code "92") (name "DATA11") (class "Default")
      (node (ref "IC8") (pin "5") (pinfunction "A4_5") (pintype "bidirectional"))
      (node (ref "X2") (pin "A30") (pinfunction "B_A30") (pintype "passive"))
    )
    (net (code "93") (name "DATA12") (class "Default")
      (node (ref "IC8") (pin "6") (pinfunction "A5_6") (pintype "bidirectional"))
      (node (ref "X2") (pin "B3") (pinfunction "B_B3") (pintype "passive"))
    )
    (net (code "94") (name "DATA13") (class "Default")
      (node (ref "IC8") (pin "7") (pinfunction "A6_7") (pintype "bidirectional"))
      (node (ref "X2") (pin "B4") (pinfunction "B_B4") (pintype "passive"))
    )
    (net (code "95") (name "DATA14") (class "Default")
      (node (ref "IC8") (pin "8") (pinfunction "A7_8") (pintype "bidirectional"))
      (node (ref "X2") (pin "B5") (pinfunction "B_B5") (pintype "passive"))
    )
    (net (code "96") (name "DATA15") (class "Default")
      (node (ref "IC8") (pin "9") (pinfunction "A8_9") (pintype "bidirectional"))
      (node (ref "X2") (pin "B6") (pinfunction "B_B6") (pintype "passive"))
    )
    (net (code "97") (name "FP-ADATA0") (class "Default")
      (node (ref "IC12") (pin "18") (pinfunction "Y1_18") (pintype "tri_state"))
      (node (ref "JP6") (pin "3") (pinfunction "3_3") (pintype "passive"))
    )
    (net (code "98") (name "FP-ADATA1") (class "Default")
      (node (ref "IC12") (pin "16") (pinfunction "Y2_16") (pintype "tri_state"))
      (node (ref "JP6") (pin "5") (pinfunction "5_5") (pintype "passive"))
    )
    (net (code "99") (name "FP-ADATA2") (class "Default")
      (node (ref "IC12") (pin "14") (pinfunction "Y3_14") (pintype "tri_state"))
      (node (ref "JP6") (pin "7") (pinfunction "7_7") (pintype "passive"))
    )
    (net (code "100") (name "FP-ADATA3") (class "Default")
      (node (ref "IC12") (pin "12") (pinfunction "Y4_12") (pintype "tri_state"))
      (node (ref "JP6") (pin "9") (pinfunction "9_9") (pintype "passive"))
    )
    (net (code "101") (name "FP-ADATA4") (class "Default")
      (node (ref "IC12") (pin "9") (pinfunction "Y1_9") (pintype "tri_state"))
      (node (ref "JP6") (pin "11") (pinfunction "11_11") (pintype "passive"))
    )
    (net (code "102") (name "FP-ADATA5") (class "Default")
      (node (ref "IC12") (pin "7") (pinfunction "Y2_7") (pintype "tri_state"))
      (node (ref "JP6") (pin "13") (pinfunction "13_13") (pintype "passive"))
    )
    (net (code "103") (name "FP-ADATA6") (class "Default")
      (node (ref "IC12") (pin "5") (pinfunction "Y3_5") (pintype "tri_state"))
      (node (ref "JP6") (pin "15") (pinfunction "15_15") (pintype "passive"))
    )
    (net (code "104") (name "FP-ADATA7") (class "Default")
      (node (ref "IC12") (pin "3") (pinfunction "Y4_3") (pintype "tri_state"))
      (node (ref "JP6") (pin "17") (pinfunction "17_17") (pintype "passive"))
    )
    (net (code "105") (name "FP-ADATA8") (class "Default")
      (node (ref "IC11") (pin "18") (pinfunction "Y1_18") (pintype "tri_state"))
      (node (ref "JP6") (pin "4") (pinfunction "4_4") (pintype "passive"))
    )
    (net (code "106") (name "FP-ADATA9") (class "Default")
      (node (ref "IC11") (pin "16") (pinfunction "Y2_16") (pintype "tri_state"))
      (node (ref "JP6") (pin "6") (pinfunction "6_6") (pintype "passive"))
    )
    (net (code "107") (name "FP-ADATA10") (class "Default")
      (node (ref "IC11") (pin "14") (pinfunction "Y3_14") (pintype "tri_state"))
      (node (ref "JP6") (pin "8") (pinfunction "8_8") (pintype "passive"))
    )
    (net (code "108") (name "FP-ADATA11") (class "Default")
      (node (ref "IC11") (pin "12") (pinfunction "Y4_12") (pintype "tri_state"))
      (node (ref "JP6") (pin "10") (pinfunction "10_10") (pintype "passive"))
    )
    (net (code "109") (name "FP-ADATA12") (class "Default")
      (node (ref "IC11") (pin "9") (pinfunction "Y1_9") (pintype "tri_state"))
      (node (ref "JP6") (pin "12") (pinfunction "12_12") (pintype "passive"))
    )
    (net (code "110") (name "FP-ADATA13") (class "Default")
      (node (ref "IC11") (pin "7") (pinfunction "Y2_7") (pintype "tri_state"))
      (node (ref "JP6") (pin "14") (pinfunction "14_14") (pintype "passive"))
    )
    (net (code "111") (name "FP-ADATA14") (class "Default")
      (node (ref "IC11") (pin "5") (pinfunction "Y3_5") (pintype "tri_state"))
      (node (ref "JP6") (pin "16") (pinfunction "16_16") (pintype "passive"))
    )
    (net (code "112") (name "FP-ADATA15") (class "Default")
      (node (ref "IC11") (pin "3") (pinfunction "Y4_3") (pintype "tri_state"))
      (node (ref "JP6") (pin "18") (pinfunction "18_18") (pintype "passive"))
    )
    (net (code "113") (name "FP-CLK0H") (class "Default")
      (node (ref "IC34") (pin "5") (pinfunction "Y3_5") (pintype "tri_state"))
      (node (ref "JP6") (pin "23") (pinfunction "23_23") (pintype "passive"))
    )
    (net (code "114") (name "FP-CLK0L") (class "Default")
      (node (ref "IC34") (pin "3") (pinfunction "Y4_3") (pintype "tri_state"))
      (node (ref "JP6") (pin "25") (pinfunction "25_25") (pintype "passive"))
    )
    (net (code "115") (name "FP-CLK1H") (class "Default")
      (node (ref "IC34") (pin "9") (pinfunction "Y1_9") (pintype "tri_state"))
      (node (ref "JP6") (pin "19") (pinfunction "19_19") (pintype "passive"))
    )
    (net (code "116") (name "FP-CLK1L") (class "Default")
      (node (ref "IC34") (pin "7") (pinfunction "Y2_7") (pintype "tri_state"))
      (node (ref "JP6") (pin "21") (pinfunction "21_21") (pintype "passive"))
    )
    (net (code "117") (name "FP-CLK2H") (class "Default")
      (node (ref "IC33") (pin "16") (pinfunction "Y2_16") (pintype "tri_state"))
      (node (ref "JP6") (pin "24") (pinfunction "24_24") (pintype "passive"))
    )
    (net (code "118") (name "FP-CLK2L") (class "Default")
      (node (ref "IC33") (pin "18") (pinfunction "Y1_18") (pintype "tri_state"))
      (node (ref "JP6") (pin "26") (pinfunction "26_26") (pintype "passive"))
    )
    (net (code "119") (name "FP-CLK3H") (class "Default")
      (node (ref "IC33") (pin "12") (pinfunction "Y4_12") (pintype "tri_state"))
      (node (ref "JP6") (pin "20") (pinfunction "20_20") (pintype "passive"))
    )
    (net (code "120") (name "FP-CLK3L") (class "Default")
      (node (ref "IC33") (pin "14") (pinfunction "Y3_14") (pintype "tri_state"))
      (node (ref "JP6") (pin "22") (pinfunction "22_22") (pintype "passive"))
    )
    (net (code "121") (name "FP-CLK4H") (class "Default")
      (node (ref "IC34") (pin "14") (pinfunction "Y3_14") (pintype "tri_state"))
      (node (ref "JP6") (pin "31") (pinfunction "31_31") (pintype "passive"))
    )
    (net (code "122") (name "FP-CLK4L") (class "Default")
      (node (ref "IC34") (pin "12") (pinfunction "Y4_12") (pintype "tri_state"))
      (node (ref "JP6") (pin "33") (pinfunction "33_33") (pintype "passive"))
    )
    (net (code "123") (name "FP-CLK5H") (class "Default")
      (node (ref "IC34") (pin "18") (pinfunction "Y1_18") (pintype "tri_state"))
      (node (ref "JP6") (pin "27") (pinfunction "27_27") (pintype "passive"))
    )
    (net (code "124") (name "FP-CLK5L") (class "Default")
      (node (ref "IC34") (pin "16") (pinfunction "Y2_16") (pintype "tri_state"))
      (node (ref "JP6") (pin "29") (pinfunction "29_29") (pintype "passive"))
    )
    (net (code "125") (name "FP-CLK6H") (class "Default")
      (node (ref "IC33") (pin "7") (pinfunction "Y2_7") (pintype "tri_state"))
      (node (ref "JP6") (pin "32") (pinfunction "32_32") (pintype "passive"))
    )
    (net (code "126") (name "FP-CLK6L") (class "Default")
      (node (ref "IC33") (pin "9") (pinfunction "Y1_9") (pintype "tri_state"))
      (node (ref "JP6") (pin "34") (pinfunction "34_34") (pintype "passive"))
    )
    (net (code "127") (name "FP-CLK7H") (class "Default")
      (node (ref "IC33") (pin "3") (pinfunction "Y4_3") (pintype "tri_state"))
      (node (ref "JP6") (pin "28") (pinfunction "28_28") (pintype "passive"))
    )
    (net (code "128") (name "FP-CLK7L") (class "Default")
      (node (ref "IC33") (pin "5") (pinfunction "Y3_5") (pintype "tri_state"))
      (node (ref "JP6") (pin "30") (pinfunction "30_30") (pintype "passive"))
    )
    (net (code "129") (name "GND") (class "Default")
      (node (ref "C1") (pin "2") (pinfunction "2_2") (pintype "passive"))
      (node (ref "C10") (pin "2") (pinfunction "2_2") (pintype "passive"))
      (node (ref "C11") (pin "2") (pinfunction "2_2") (pintype "passive"))
      (node (ref "C12") (pin "2") (pinfunction "2_2") (pintype "passive"))
      (node (ref "C13") (pin "2") (pinfunction "2_2") (pintype "passive"))
      (node (ref "C14") (pin "2") (pinfunction "2_2") (pintype "passive"))
      (node (ref "C15") (pin "2") (pinfunction "2_2") (pintype "passive"))
      (node (ref "C16") (pin "2") (pinfunction "2_2") (pintype "passive"))
      (node (ref "C17") (pin "2") (pinfunction "2_2") (pintype "passive"))
      (node (ref "C18") (pin "2") (pinfunction "2_2") (pintype "passive"))
      (node (ref "C19") (pin "2") (pinfunction "2_2") (pintype "passive"))
      (node (ref "C2") (pin "2") (pinfunction "2_2") (pintype "passive"))
      (node (ref "C20") (pin "2") (pinfunction "2_2") (pintype "passive"))
      (node (ref "C21") (pin "2") (pinfunction "2_2") (pintype "passive"))
      (node (ref "C22") (pin "2") (pinfunction "2_2") (pintype "passive"))
      (node (ref "C23") (pin "2") (pinfunction "2_2") (pintype "passive"))
      (node (ref "C24") (pin "2") (pinfunction "2_2") (pintype "passive"))
      (node (ref "C25") (pin "2") (pinfunction "2_2") (pintype "passive"))
      (node (ref "C26") (pin "2") (pinfunction "2_2") (pintype "passive"))
      (node (ref "C27") (pin "2") (pinfunction "2_2") (pintype "passive"))
      (node (ref "C28") (pin "2") (pinfunction "2_2") (pintype "passive"))
      (node (ref "C29") (pin "2") (pinfunction "2_2") (pintype "passive"))
      (node (ref "C3") (pin "2") (pinfunction "2_2") (pintype "passive"))
      (node (ref "C30") (pin "2") (pinfunction "2_2") (pintype "passive"))
      (node (ref "C31") (pin "2") (pinfunction "2_2") (pintype "passive"))
      (node (ref "C32") (pin "2") (pinfunction "2_2") (pintype "passive"))
      (node (ref "C33") (pin "2") (pinfunction "2_2") (pintype "passive"))
      (node (ref "C34") (pin "2") (pinfunction "2_2") (pintype "passive"))
      (node (ref "C35") (pin "2") (pinfunction "2_2") (pintype "passive"))
      (node (ref "C36") (pin "2") (pinfunction "2_2") (pintype "passive"))
      (node (ref "C37") (pin "2") (pinfunction "2_2") (pintype "passive"))
      (node (ref "C4") (pin "2") (pinfunction "2_2") (pintype "passive"))
      (node (ref "C5") (pin "2") (pinfunction "2_2") (pintype "passive"))
      (node (ref "C6") (pin "2") (pinfunction "2_2") (pintype "passive"))
      (node (ref "C7") (pin "2") (pinfunction "2_2") (pintype "passive"))
      (node (ref "C8") (pin "2") (pinfunction "2_2") (pintype "passive"))
      (node (ref "C9") (pin "2") (pinfunction "2_2") (pintype "passive"))
      (node (ref "IC5") (pin "10") (pinfunction "I1_10") (pintype "input"))
      (node (ref "IC5") (pin "12") (pinfunction "I0_12") (pintype "input"))
      (node (ref "IC5") (pin "13") (pinfunction "I1_13") (pintype "input"))
      (node (ref "IC5") (pin "9") (pinfunction "I0_9") (pintype "input"))
      (node (ref "J1") (pin "2") (pinfunction "2_2") (pintype "passive"))
      (node (ref "JP6") (pin "39") (pinfunction "39_39") (pintype "passive"))
      (node (ref "JP6") (pin "40") (pinfunction "40_40") (pintype "passive"))
      (node (ref "PWR") (pin "K") (pinfunction "C_K") (pintype "passive"))
      (node (ref "X2") (pin "A1") (pinfunction "B_A1") (pintype "passive"))
      (node (ref "X2") (pin "A32") (pinfunction "B_A32") (pintype "passive"))
      (node (ref "X2") (pin "B1") (pinfunction "B_B1") (pintype "passive"))
      (node (ref "X2") (pin "B32") (pinfunction "B_B32") (pintype "passive"))
      (node (ref "X2") (pin "C1") (pinfunction "B_C1") (pintype "passive"))
      (node (ref "X2") (pin "C32") (pinfunction "B_C32") (pintype "passive"))
    )
    (net (code "130") (name "H{slash}L-SWAP") (class "Default")
      (node (ref "IC1") (pin "13") (pinfunction "I_13") (pintype "input"))
      (node (ref "IC6") (pin "10") (pinfunction "I1_10") (pintype "input"))
      (node (ref "X2") (pin "C25") (pinfunction "B_C25") (pintype "passive"))
    )
    (net (code "131") (name "IN") (class "Default")
      (node (ref "X2") (pin "C26") (pinfunction "B_C26") (pintype "passive"))
    )
    (net (code "132") (name "INT") (class "Default")
      (node (ref "X2") (pin "B29") (pinfunction "B_B29") (pintype "passive"))
    )
    (net (code "133") (name "INTA") (class "Default")
      (node (ref "X2") (pin "B30") (pinfunction "B_B30") (pintype "passive"))
    )
    (net (code "134") (name "I{slash}D-REG-DN") (class "Default")
      (node (ref "X2") (pin "C5") (pinfunction "B_C5") (pintype "passive"))
    )
    (net (code "135") (name "I{slash}D-REG-LD") (class "Default")
      (node (ref "X2") (pin "C3") (pinfunction "B_C3") (pintype "passive"))
    )
    (net (code "136") (name "I{slash}D-REG-RD") (class "Default")
      (node (ref "X2") (pin "C4") (pinfunction "B_C4") (pintype "passive"))
    )
    (net (code "137") (name "I{slash}D-REG-UP") (class "Default")
      (node (ref "X2") (pin "C6") (pinfunction "B_C6") (pintype "passive"))
    )
    (net (code "138") (name "I{slash}O-ADDR") (class "Default")
      (node (ref "X2") (pin "B28") (pinfunction "B_B28") (pintype "passive"))
    )
    (net (code "139") (name "I{slash}O-RD") (class "Default")
      (node (ref "X2") (pin "B27") (pinfunction "B_B27") (pintype "passive"))
    )
    (net (code "140") (name "I{slash}O-WR") (class "Default")
      (node (ref "X2") (pin "B26") (pinfunction "B_B26") (pintype "passive"))
    )
    (net (code "141") (name "MEM-RD") (class "Default")
      (node (ref "X2") (pin "B25") (pinfunction "B_B25") (pintype "passive"))
    )
    (net (code "142") (name "MEM-WR") (class "Default")
      (node (ref "X2") (pin "B24") (pinfunction "B_B24") (pintype "passive"))
    )
    (net (code "143") (name "Net-(IC1F-O)") (class "Default")
      (node (ref "IC1") (pin "12") (pinfunction "O_12") (pintype "output"))
      (node (ref "IC6") (pin "1") (pinfunction "I0_1") (pintype "input"))
    )
    (net (code "144") (name "Net-(IC2A-G1)") (class "Default")
      (node (ref "IC2") (pin "6") (pinfunction "G1_6") (pintype "input"))
      (node (ref "IC3") (pin "6") (pinfunction "G1_6") (pintype "input"))
      (node (ref "R2") (pin "1") (pinfunction "1_1") (pintype "passive"))
    )
    (net (code "145") (name "Net-(IC4A-O)") (class "Default")
      (node (ref "IC4") (pin "3") (pinfunction "O_3") (pintype "output"))
      (node (ref "IC4") (pin "4") (pinfunction "I0_4") (pintype "input"))
    )
    (net (code "146") (name "Net-(IC4B-O)") (class "Default")
      (node (ref "IC4") (pin "6") (pinfunction "O_6") (pintype "output"))
      (node (ref "JP1") (pin "1") (pinfunction "1_1") (pintype "passive"))
    )
    (net (code "147") (name "Net-(IC4C-O)") (class "Default")
      (node (ref "IC4") (pin "8") (pinfunction "O_8") (pintype "output"))
      (node (ref "JP1") (pin "3") (pinfunction "3_3") (pintype "passive"))
    )
    (net (code "148") (name "Net-(IC4D-I0)") (class "Default")
      (node (ref "IC4") (pin "12") (pinfunction "I0_12") (pintype "input"))
      (node (ref "IC6") (pin "11") (pinfunction "O_11") (pintype "output"))
    )
    (net (code "149") (name "Net-(IC4D-O)") (class "Default")
      (node (ref "IC4") (pin "11") (pinfunction "O_11") (pintype "output"))
      (node (ref "JP2") (pin "1") (pinfunction "1_1") (pintype "passive"))
    )
    (net (code "150") (name "Net-(IC5A-O)") (class "Default")
      (node (ref "IC5") (pin "3") (pinfunction "O_3") (pintype "output"))
      (node (ref "IC5") (pin "5") (pinfunction "I1_5") (pintype "input"))
      (node (ref "IC6") (pin "2") (pinfunction "I1_2") (pintype "input"))
      (node (ref "IC6") (pin "9") (pinfunction "I0_9") (pintype "input"))
    )
    (net (code "151") (name "Net-(IC5B-O)") (class "Default")
      (node (ref "IC5") (pin "6") (pinfunction "O_6") (pintype "output"))
      (node (ref "IC8") (pin "19") (pinfunction "G_19") (pintype "input"))
    )
    (net (code "152") (name "Net-(IC6A-O)") (class "Default")
      (node (ref "IC6") (pin "3") (pinfunction "O_3") (pintype "output"))
      (node (ref "IC7") (pin "19") (pinfunction "G_19") (pintype "input"))
    )
    (net (code "153") (name "Net-(IC6B-O)") (class "Default")
      (node (ref "IC6") (pin "6") (pinfunction "O_6") (pintype "output"))
      (node (ref "JP2") (pin "3") (pinfunction "3_3") (pintype "passive"))
    )
    (net (code "154") (name "Net-(IC6C-O)") (class "Default")
      (node (ref "IC6") (pin "8") (pinfunction "O_8") (pintype "output"))
      (node (ref "IC9") (pin "19") (pinfunction "G_19") (pintype "input"))
    )
    (net (code "155") (name "Net-(IC10A-OC)") (class "Default")
      (node (ref "IC10") (pin "1") (pinfunction "OC_1") (pintype "input"))
      (node (ref "IC32") (pin "3") (pinfunction "O_3") (pintype "output"))
    )
    (net (code "156") (name "Net-(IC11A-G)") (class "Default")
      (node (ref "IC11") (pin "1") (pinfunction "G_1") (pintype "input"))
      (node (ref "IC11") (pin "19") (pinfunction "G_19") (pintype "input"))
      (node (ref "IC12") (pin "1") (pinfunction "G_1") (pintype "input"))
      (node (ref "IC12") (pin "19") (pinfunction "G_19") (pintype "input"))
      (node (ref "IC33") (pin "1") (pinfunction "G_1") (pintype "input"))
      (node (ref "IC33") (pin "19") (pinfunction "G_19") (pintype "input"))
      (node (ref "IC34") (pin "1") (pinfunction "G_1") (pintype "input"))
      (node (ref "IC34") (pin "19") (pinfunction "G_19") (pintype "input"))
      (node (ref "J1") (pin "1") (pinfunction "1_1") (pintype "passive"))
      (node (ref "R1") (pin "1") (pinfunction "1_1") (pintype "passive"))
    )
    (net (code "157") (name "Net-(IC13A-O)") (class "Default")
      (node (ref "IC13") (pin "3") (pinfunction "O_3") (pintype "output"))
      (node (ref "IC15") (pin "1") (pinfunction "OC_1") (pintype "input"))
    )
    (net (code "158") (name "Net-(IC13B-O)") (class "Default")
      (node (ref "IC13") (pin "6") (pinfunction "O_6") (pintype "output"))
      (node (ref "IC16") (pin "1") (pinfunction "OC_1") (pintype "input"))
    )
    (net (code "159") (name "Net-(IC13C-O)") (class "Default")
      (node (ref "IC13") (pin "8") (pinfunction "O_8") (pintype "output"))
      (node (ref "IC17") (pin "1") (pinfunction "OC_1") (pintype "input"))
    )
    (net (code "160") (name "Net-(IC13D-O)") (class "Default")
      (node (ref "IC13") (pin "11") (pinfunction "O_11") (pintype "output"))
      (node (ref "IC18") (pin "1") (pinfunction "OC_1") (pintype "input"))
    )
    (net (code "161") (name "Net-(IC19A-O)") (class "Default")
      (node (ref "IC19") (pin "3") (pinfunction "O_3") (pintype "output"))
      (node (ref "IC21") (pin "1") (pinfunction "OC_1") (pintype "input"))
    )
    (net (code "162") (name "Net-(IC19B-O)") (class "Default")
      (node (ref "IC19") (pin "6") (pinfunction "O_6") (pintype "output"))
      (node (ref "IC22") (pin "1") (pinfunction "OC_1") (pintype "input"))
    )
    (net (code "163") (name "Net-(IC19C-O)") (class "Default")
      (node (ref "IC19") (pin "8") (pinfunction "O_8") (pintype "output"))
      (node (ref "IC23") (pin "1") (pinfunction "OC_1") (pintype "input"))
    )
    (net (code "164") (name "Net-(IC19D-O)") (class "Default")
      (node (ref "IC19") (pin "11") (pinfunction "O_11") (pintype "output"))
      (node (ref "IC24") (pin "1") (pinfunction "OC_1") (pintype "input"))
    )
    (net (code "165") (name "Net-(IC25A-OC)") (class "Default")
      (node (ref "IC25") (pin "1") (pinfunction "OC_1") (pintype "input"))
      (node (ref "IC32") (pin "6") (pinfunction "O_6") (pintype "output"))
    )
    (net (code "166") (name "Net-(IC26A-OC)") (class "Default")
      (node (ref "IC26") (pin "1") (pinfunction "OC_1") (pintype "input"))
      (node (ref "IC37") (pin "3") (pinfunction "O_3") (pintype "output"))
    )
    (net (code "167") (name "Net-(IC27A-OC)") (class "Default")
      (node (ref "IC27") (pin "1") (pinfunction "OC_1") (pintype "input"))
      (node (ref "IC37") (pin "6") (pinfunction "O_6") (pintype "output"))
    )
    (net (code "168") (name "Net-(IC28A-OC)") (class "Default")
      (node (ref "IC28") (pin "1") (pinfunction "OC_1") (pintype "input"))
      (node (ref "IC32") (pin "8") (pinfunction "O_8") (pintype "output"))
    )
    (net (code "169") (name "Net-(IC29A-OC)") (class "Default")
      (node (ref "IC29") (pin "1") (pinfunction "OC_1") (pintype "input"))
      (node (ref "IC32") (pin "11") (pinfunction "O_11") (pintype "output"))
    )
    (net (code "170") (name "Net-(IC30A-OC)") (class "Default")
      (node (ref "IC30") (pin "1") (pinfunction "OC_1") (pintype "input"))
      (node (ref "IC37") (pin "8") (pinfunction "O_8") (pintype "output"))
    )
    (net (code "171") (name "Net-(IC31A-OC)") (class "Default")
      (node (ref "IC31") (pin "1") (pinfunction "OC_1") (pintype "input"))
      (node (ref "IC37") (pin "11") (pinfunction "O_11") (pintype "output"))
    )
    (net (code "172") (name "Net-(PWR-PadA)") (class "Default")
      (node (ref "PWR") (pin "A") (pinfunction "A_A") (pintype "passive"))
      (node (ref "R3") (pin "1") (pinfunction "1_1") (pintype "passive"))
    )
    (net (code "173") (name "OUT") (class "Default")
      (node (ref "X2") (pin "C27") (pinfunction "B_C27") (pintype "passive"))
    )
    (net (code "174") (name "REG-BRD-LD-ID") (class "Default")
      (node (ref "IC6") (pin "12") (pinfunction "I0_12") (pintype "input"))
      (node (ref "IC6") (pin "13") (pinfunction "I1_13") (pintype "input"))
      (node (ref "IC6") (pin "5") (pinfunction "I1_5") (pintype "input"))
      (node (ref "X2") (pin "B16") (pinfunction "B_B16") (pintype "passive"))
    )
    (net (code "175") (name "REG-BRD-RD-ID") (class "Default")
      (node (ref "IC4") (pin "1") (pinfunction "I0_1") (pintype "input"))
      (node (ref "IC4") (pin "10") (pinfunction "I1_10") (pintype "input"))
      (node (ref "IC4") (pin "2") (pinfunction "I1_2") (pintype "input"))
      (node (ref "X2") (pin "B12") (pinfunction "B_B12") (pintype "passive"))
    )
    (net (code "176") (name "REG-FUNC-LD") (class "Default")
      (node (ref "IC4") (pin "13") (pinfunction "I1_13") (pintype "input"))
      (node (ref "IC6") (pin "4") (pinfunction "I0_4") (pintype "input"))
      (node (ref "X2") (pin "B7") (pinfunction "B_B7") (pintype "passive"))
    )
    (net (code "177") (name "REG-FUNC-RD") (class "Default")
      (node (ref "IC4") (pin "5") (pinfunction "I1_5") (pintype "input"))
      (node (ref "IC4") (pin "9") (pinfunction "I0_9") (pintype "input"))
      (node (ref "X2") (pin "B8") (pinfunction "B_B8") (pintype "passive"))
    )
    (net (code "178") (name "REG-LD-HI") (class "Default")
      (node (ref "IC1") (pin "9") (pinfunction "I_9") (pintype "input"))
      (node (ref "X2") (pin "B23") (pinfunction "B_B23") (pintype "passive"))
    )
    (net (code "179") (name "REG-LD-ID0") (class "Default")
      (node (ref "IC3") (pin "1") (pinfunction "A_1") (pintype "input"))
      (node (ref "X2") (pin "B17") (pinfunction "B_B17") (pintype "passive"))
    )
    (net (code "180") (name "REG-LD-ID1") (class "Default")
      (node (ref "IC3") (pin "2") (pinfunction "B_2") (pintype "input"))
      (node (ref "X2") (pin "B18") (pinfunction "B_B18") (pintype "passive"))
    )
    (net (code "181") (name "REG-LD-ID2") (class "Default")
      (node (ref "IC3") (pin "3") (pinfunction "C_3") (pintype "input"))
      (node (ref "X2") (pin "B19") (pinfunction "B_B19") (pintype "passive"))
    )
    (net (code "182") (name "REG-LD-LO") (class "Default")
      (node (ref "IC1") (pin "3") (pinfunction "I_3") (pintype "input"))
      (node (ref "X2") (pin "B21") (pinfunction "B_B21") (pintype "passive"))
    )
    (net (code "183") (name "REG-RD-HI") (class "Default")
      (node (ref "IC1") (pin "5") (pinfunction "I_5") (pintype "input"))
      (node (ref "X2") (pin "B22") (pinfunction "B_B22") (pintype "passive"))
    )
    (net (code "184") (name "REG-RD-ID0") (class "Default")
      (node (ref "IC2") (pin "1") (pinfunction "A_1") (pintype "input"))
      (node (ref "X2") (pin "B13") (pinfunction "B_B13") (pintype "passive"))
    )
    (net (code "185") (name "REG-RD-ID1") (class "Default")
      (node (ref "IC2") (pin "2") (pinfunction "B_2") (pintype "input"))
      (node (ref "X2") (pin "B14") (pinfunction "B_B14") (pintype "passive"))
    )
    (net (code "186") (name "REG-RD-ID2") (class "Default")
      (node (ref "IC2") (pin "3") (pinfunction "C_3") (pintype "input"))
      (node (ref "X2") (pin "B15") (pinfunction "B_B15") (pintype "passive"))
    )
    (net (code "187") (name "REG-RD-LO") (class "Default")
      (node (ref "IC1") (pin "1") (pinfunction "I_1") (pintype "input"))
      (node (ref "X2") (pin "B20") (pinfunction "B_B20") (pintype "passive"))
    )
    (net (code "188") (name "RESET") (class "Default")
      (node (ref "X2") (pin "C30") (pinfunction "B_C30") (pintype "passive"))
    )
    (net (code "189") (name "RUN") (class "Default")
      (node (ref "X2") (pin "C29") (pinfunction "B_C29") (pintype "passive"))
    )
    (net (code "190") (name "SP{slash}PC-ADDR-RD") (class "Default")
      (node (ref "X2") (pin "C10") (pinfunction "B_C10") (pintype "passive"))
    )
    (net (code "191") (name "SP{slash}PC-DATA-RD-HI") (class "Default")
      (node (ref "X2") (pin "C9") (pinfunction "B_C9") (pintype "passive"))
    )
    (net (code "192") (name "SP{slash}PC-DATA-RD-LO") (class "Default")
      (node (ref "X2") (pin "C8") (pinfunction "B_C8") (pintype "passive"))
    )
    (net (code "193") (name "SP{slash}PC-DN") (class "Default")
      (node (ref "X2") (pin "C13") (pinfunction "B_C13") (pintype "passive"))
    )
    (net (code "194") (name "SP{slash}PC-LD-HI") (class "Default")
      (node (ref "X2") (pin "C12") (pinfunction "B_C12") (pintype "passive"))
    )
    (net (code "195") (name "SP{slash}PC-LD-LO") (class "Default")
      (node (ref "X2") (pin "C11") (pinfunction "B_C11") (pintype "passive"))
    )
    (net (code "196") (name "SP{slash}PC-SEL") (class "Default")
      (node (ref "X2") (pin "C7") (pinfunction "B_C7") (pintype "passive"))
    )
    (net (code "197") (name "SP{slash}PC-UP") (class "Default")
      (node (ref "X2") (pin "C14") (pinfunction "B_C14") (pintype "passive"))
    )
    (net (code "198") (name "SR-LD") (class "Default")
      (node (ref "X2") (pin "C23") (pinfunction "B_C23") (pintype "passive"))
    )
    (net (code "199") (name "UNUSED1") (class "Default")
      (node (ref "X2") (pin "C28") (pinfunction "B_C28") (pintype "passive"))
    )
    (net (code "200") (name "UNUSED3") (class "Default")
      (node (ref "X2") (pin "B9") (pinfunction "B_B9") (pintype "passive"))
    )
    (net (code "201") (name "UNUSED4") (class "Default")
      (node (ref "X2") (pin "B10") (pinfunction "B_B10") (pintype "passive"))
    )
    (net (code "202") (name "UNUSED5") (class "Default")
      (node (ref "X2") (pin "B11") (pinfunction "B_B11") (pintype "passive"))
    )
    (net (code "203") (name "VCC") (class "Default")
      (node (ref "C1") (pin "1") (pinfunction "1_1") (pintype "passive"))
      (node (ref "C10") (pin "1") (pinfunction "1_1") (pintype "passive"))
      (node (ref "C11") (pin "1") (pinfunction "1_1") (pintype "passive"))
      (node (ref "C12") (pin "1") (pinfunction "1_1") (pintype "passive"))
      (node (ref "C13") (pin "1") (pinfunction "1_1") (pintype "passive"))
      (node (ref "C14") (pin "1") (pinfunction "1_1") (pintype "passive"))
      (node (ref "C15") (pin "1") (pinfunction "1_1") (pintype "passive"))
      (node (ref "C16") (pin "1") (pinfunction "1_1") (pintype "passive"))
      (node (ref "C17") (pin "1") (pinfunction "1_1") (pintype "passive"))
      (node (ref "C18") (pin "1") (pinfunction "1_1") (pintype "passive"))
      (node (ref "C19") (pin "1") (pinfunction "1_1") (pintype "passive"))
      (node (ref "C2") (pin "1") (pinfunction "1_1") (pintype "passive"))
      (node (ref "C20") (pin "1") (pinfunction "1_1") (pintype "passive"))
      (node (ref "C21") (pin "1") (pinfunction "1_1") (pintype "passive"))
      (node (ref "C22") (pin "1") (pinfunction "1_1") (pintype "passive"))
      (node (ref "C23") (pin "1") (pinfunction "1_1") (pintype "passive"))
      (node (ref "C24") (pin "1") (pinfunction "1_1") (pintype "passive"))
      (node (ref "C25") (pin "1") (pinfunction "1_1") (pintype "passive"))
      (node (ref "C26") (pin "1") (pinfunction "1_1") (pintype "passive"))
      (node (ref "C27") (pin "1") (pinfunction "1_1") (pintype "passive"))
      (node (ref "C28") (pin "1") (pinfunction "1_1") (pintype "passive"))
      (node (ref "C29") (pin "1") (pinfunction "1_1") (pintype "passive"))
      (node (ref "C3") (pin "1") (pinfunction "1_1") (pintype "passive"))
      (node (ref "C30") (pin "1") (pinfunction "1_1") (pintype "passive"))
      (node (ref "C31") (pin "1") (pinfunction "1_1") (pintype "passive"))
      (node (ref "C32") (pin "1") (pinfunction "1_1") (pintype "passive"))
      (node (ref "C33") (pin "1") (pinfunction "1_1") (pintype "passive"))
      (node (ref "C34") (pin "1") (pinfunction "1_1") (pintype "passive"))
      (node (ref "C35") (pin "1") (pinfunction "1_1") (pintype "passive"))
      (node (ref "C36") (pin "1") (pinfunction "1_1") (pintype "passive"))
      (node (ref "C37") (pin "1") (pinfunction "1_1") (pintype "passive"))
      (node (ref "C4") (pin "1") (pinfunction "1_1") (pintype "passive"))
      (node (ref "C5") (pin "1") (pinfunction "1_1") (pintype "passive"))
      (node (ref "C6") (pin "1") (pinfunction "1_1") (pintype "passive"))
      (node (ref "C7") (pin "1") (pinfunction "1_1") (pintype "passive"))
      (node (ref "C8") (pin "1") (pinfunction "1_1") (pintype "passive"))
      (node (ref "C9") (pin "1") (pinfunction "1_1") (pintype "passive"))
      (node (ref "IC5") (pin "4") (pinfunction "I0_4") (pintype "input"))
      (node (ref "JP6") (pin "1") (pinfunction "1_1") (pintype "passive"))
      (node (ref "JP6") (pin "2") (pinfunction "2_2") (pintype "passive"))
      (node (ref "R1") (pin "2") (pinfunction "2_2") (pintype "passive"))
      (node (ref "R2") (pin "2") (pinfunction "2_2") (pintype "passive"))
      (node (ref "R3") (pin "2") (pinfunction "2_2") (pintype "passive"))
      (node (ref "RN1") (pin "1") (pinfunction "1_1") (pintype "passive"))
      (node (ref "RN2") (pin "1") (pinfunction "1_1") (pintype "passive"))
      (node (ref "X2") (pin "A2") (pinfunction "B_A2") (pintype "passive"))
      (node (ref "X2") (pin "A31") (pinfunction "B_A31") (pintype "passive"))
      (node (ref "X2") (pin "B2") (pinfunction "B_B2") (pintype "passive"))
      (node (ref "X2") (pin "B31") (pinfunction "B_B31") (pintype "passive"))
      (node (ref "X2") (pin "C2") (pinfunction "B_C2") (pintype "passive"))
      (node (ref "X2") (pin "C31") (pinfunction "B_C31") (pintype "passive"))
    )
    (net (code "204") (name "unconnected-(IC5C-O-Pad8)") (class "Default")
      (node (ref "IC5") (pin "8") (pinfunction "O_8") (pintype "output"))
    )
    (net (code "205") (name "unconnected-(IC5D-O-Pad11)") (class "Default")
      (node (ref "IC5") (pin "11") (pinfunction "O_11") (pintype "output"))
    )
    (net (code "206") (name "unconnected-(JP6-Pad35)") (class "Default")
      (node (ref "JP6") (pin "35") (pinfunction "35_35") (pintype "passive"))
    )
    (net (code "207") (name "unconnected-(JP6-Pad36)") (class "Default")
      (node (ref "JP6") (pin "36") (pinfunction "36_36") (pintype "passive"))
    )
    (net (code "208") (name "unconnected-(JP6-Pad37)") (class "Default")
      (node (ref "JP6") (pin "37") (pinfunction "37_37") (pintype "passive"))
    )
    (net (code "209") (name "unconnected-(JP6-Pad38)") (class "Default")
      (node (ref "JP6") (pin "38") (pinfunction "38_38") (pintype "passive"))
    )
  )
)
